# fusebox.net
KiCad netlist of a schematic drawn in EAGLE
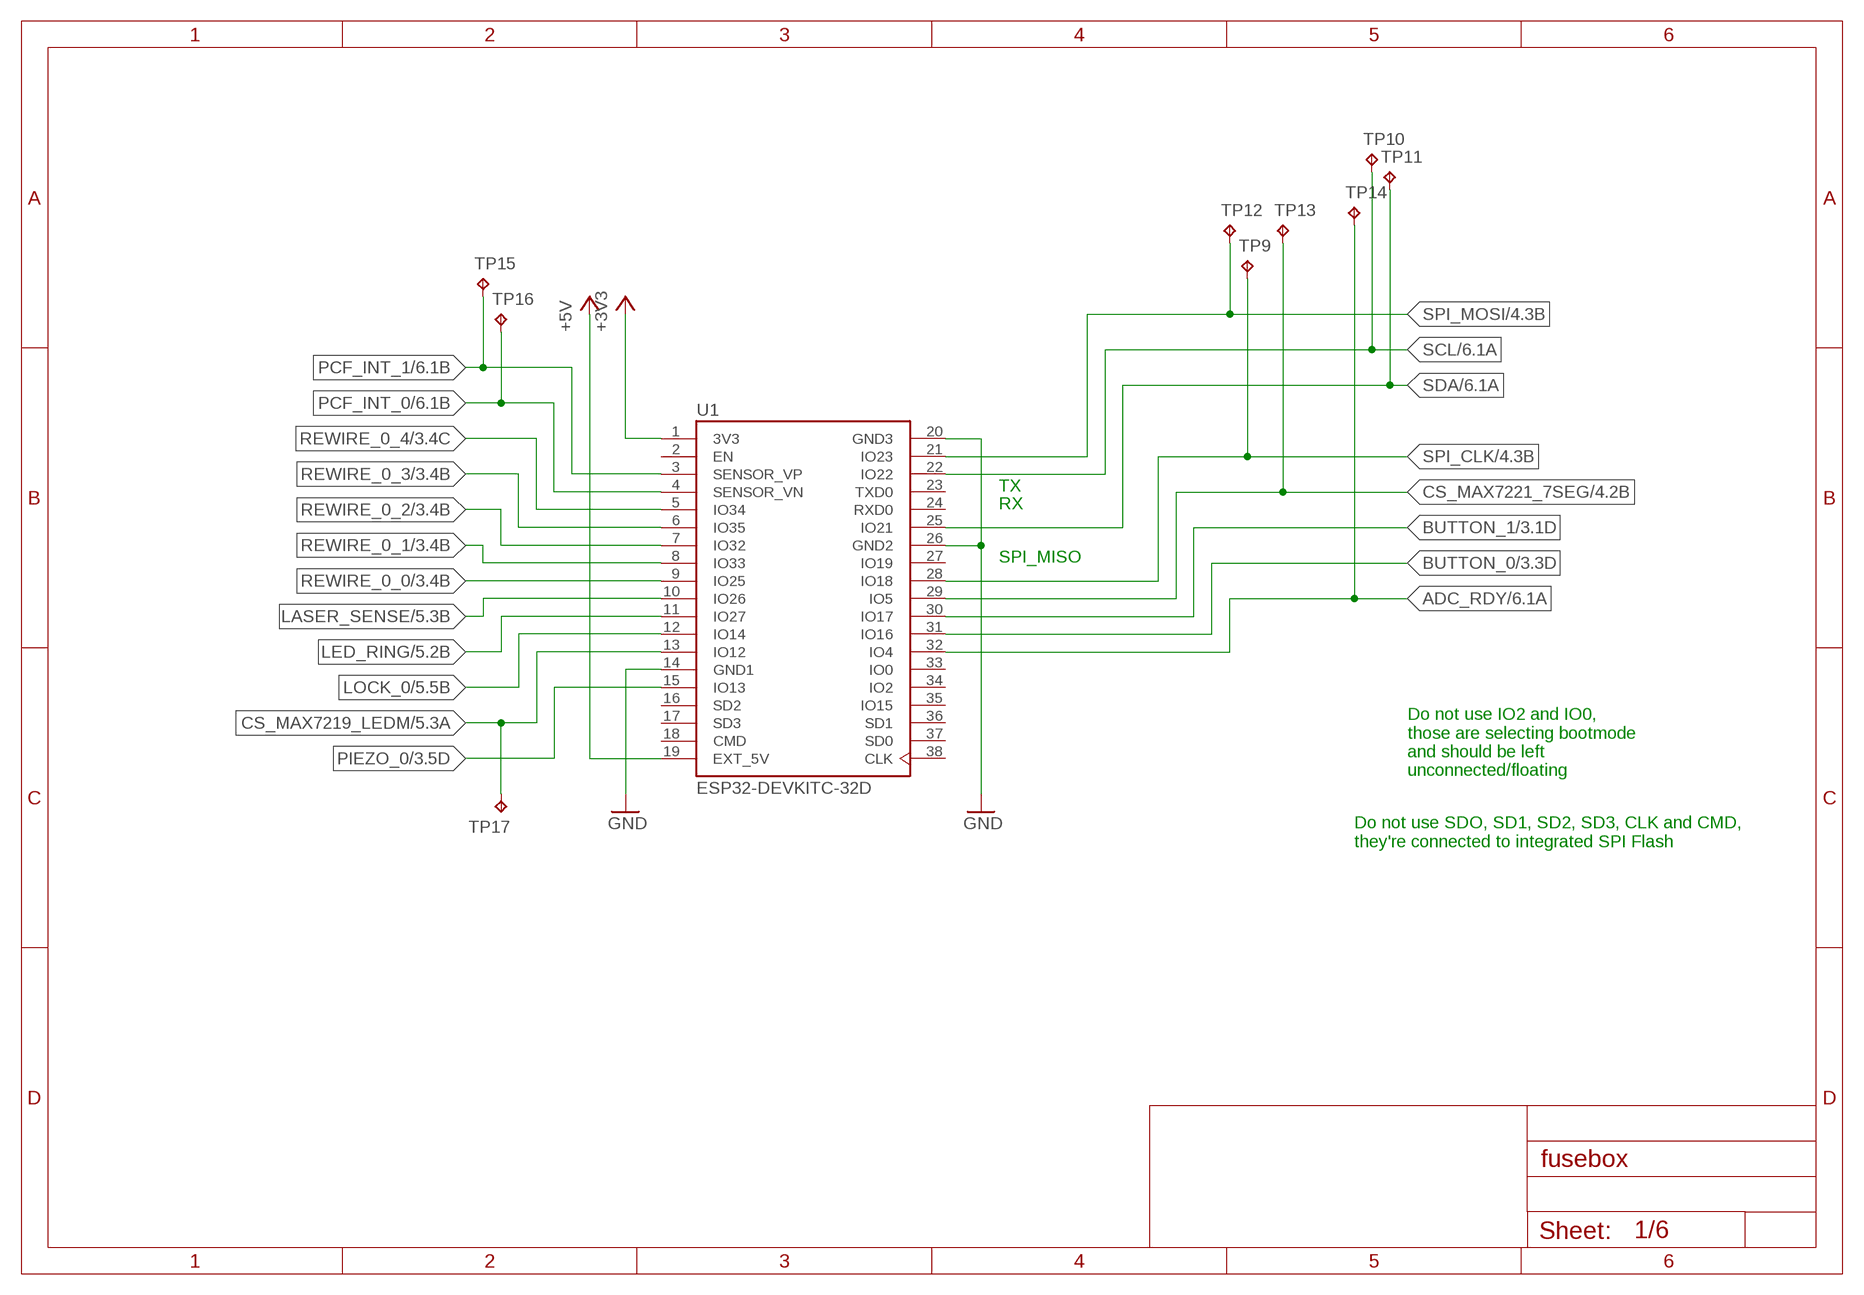
[diagram p0: schematic, sheet 1]
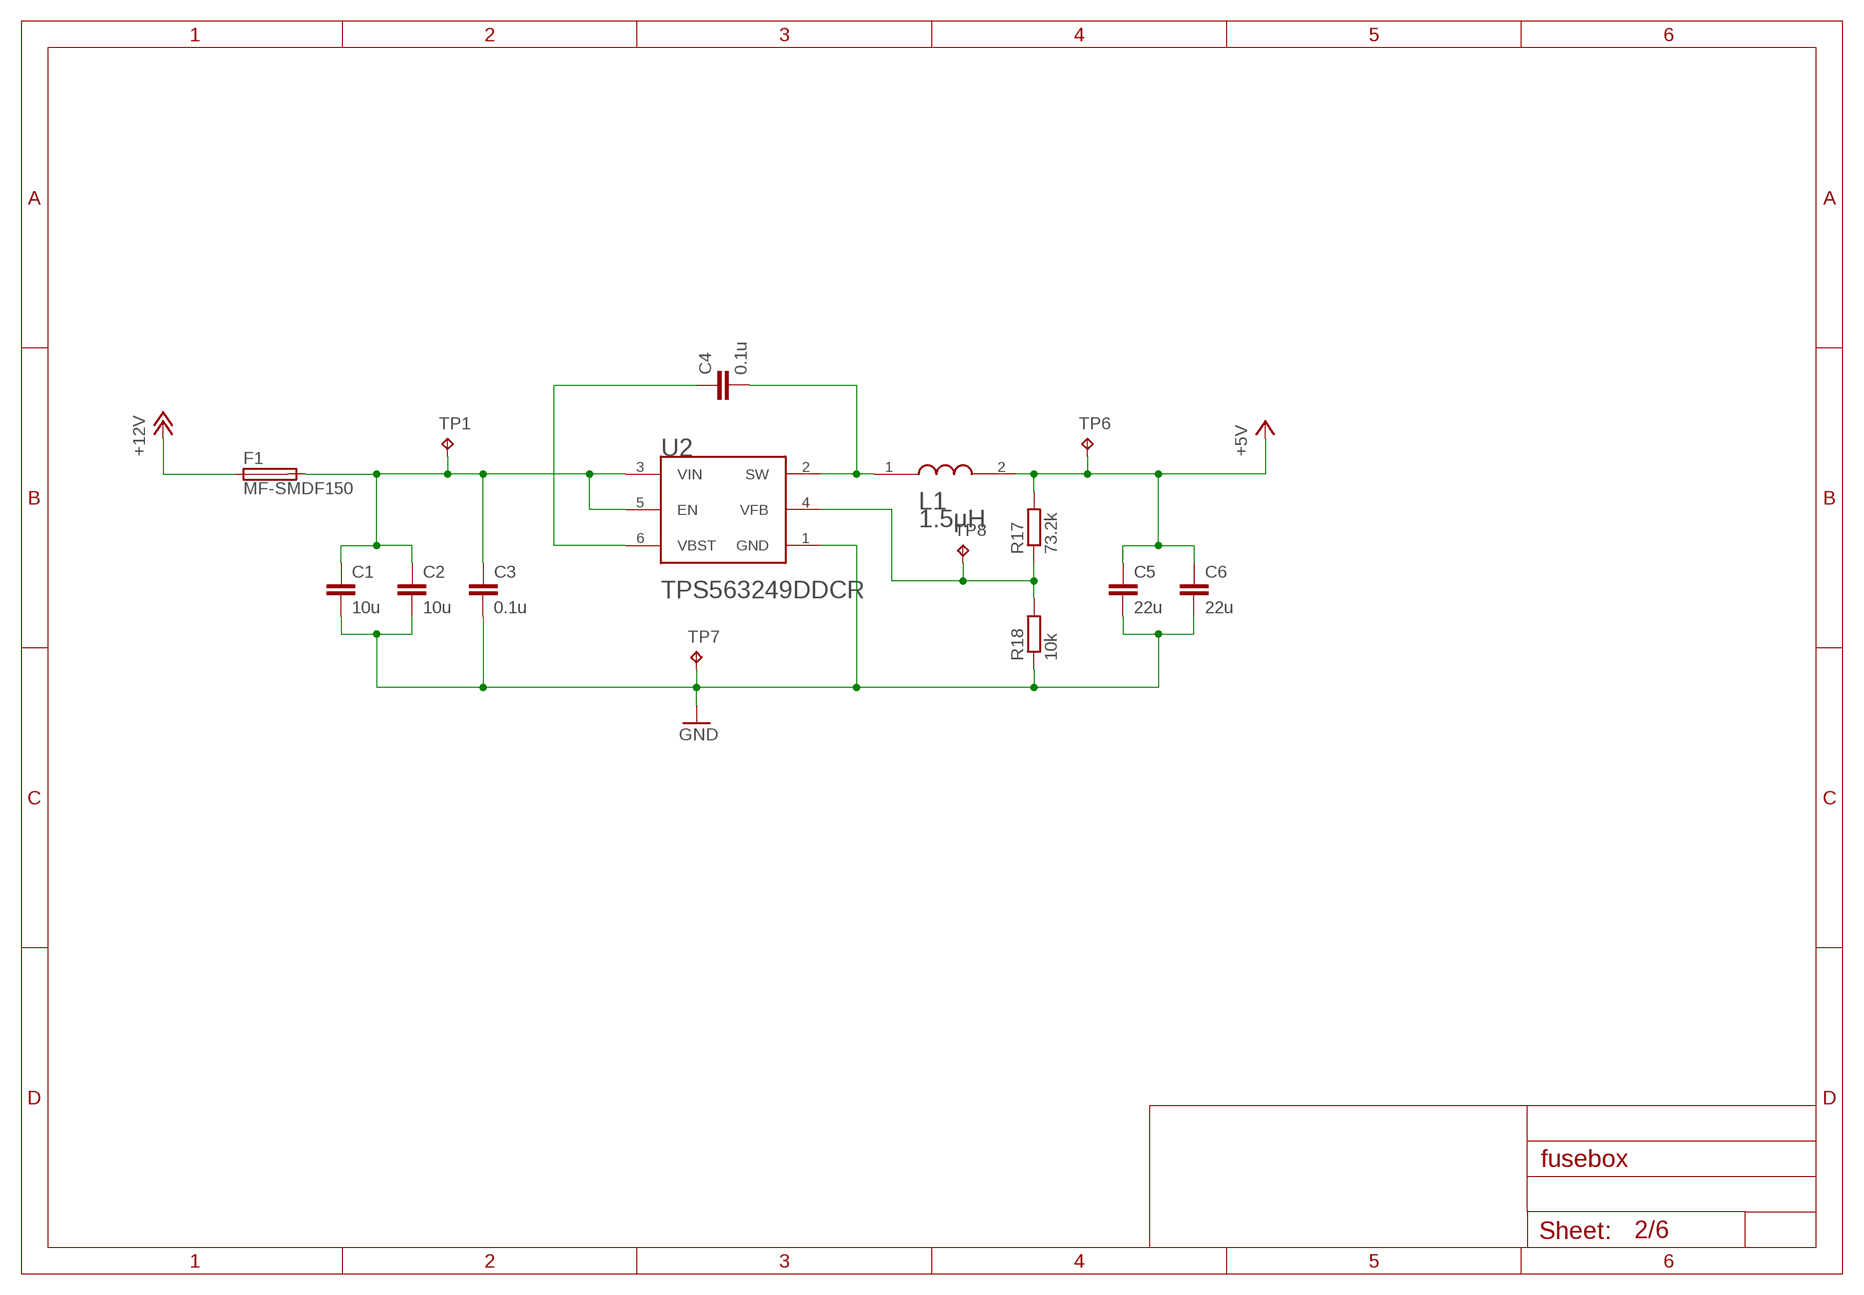
[diagram p1: schematic, sheet 2]
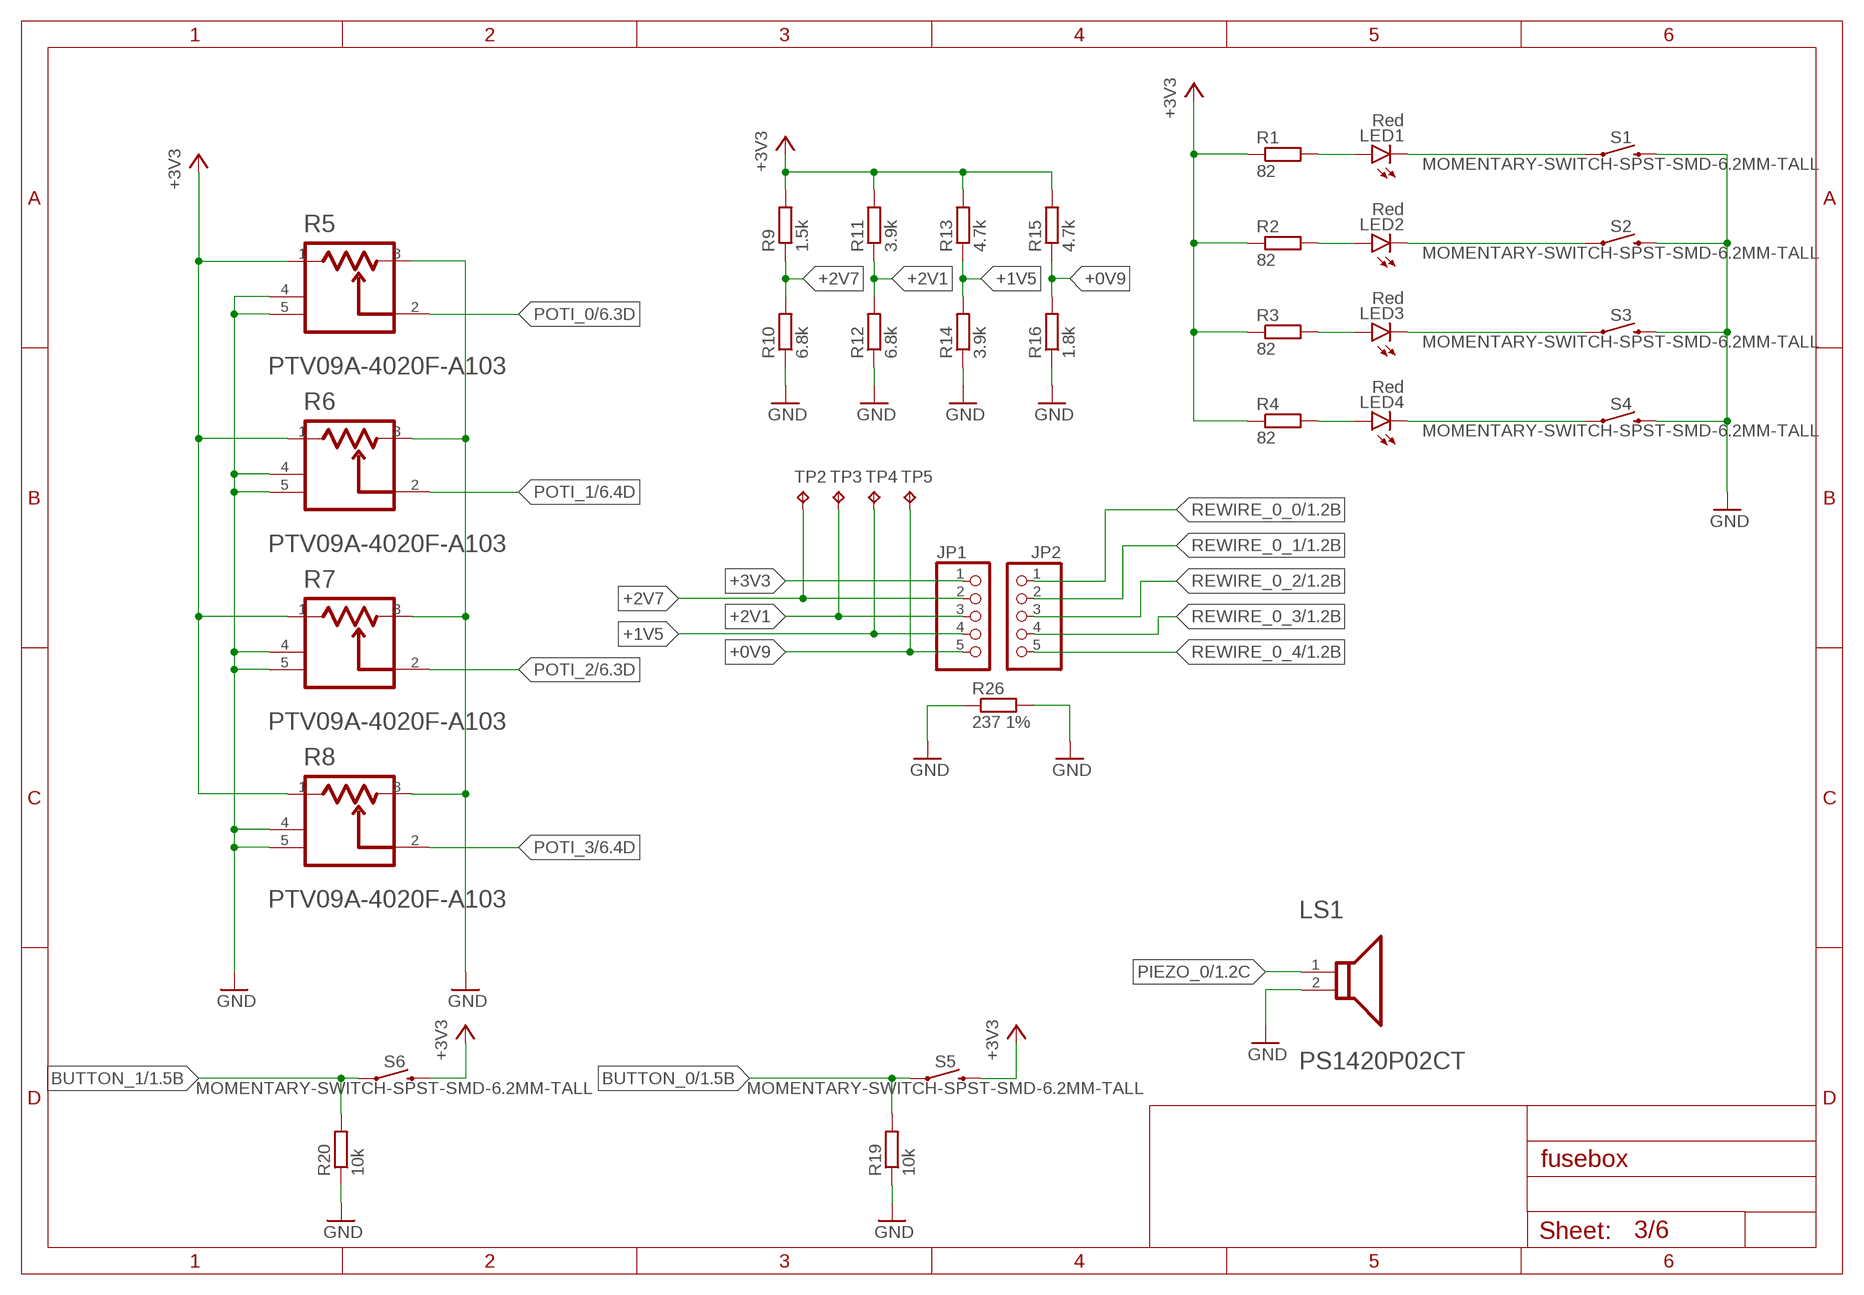
[diagram p2: schematic, sheet 3]
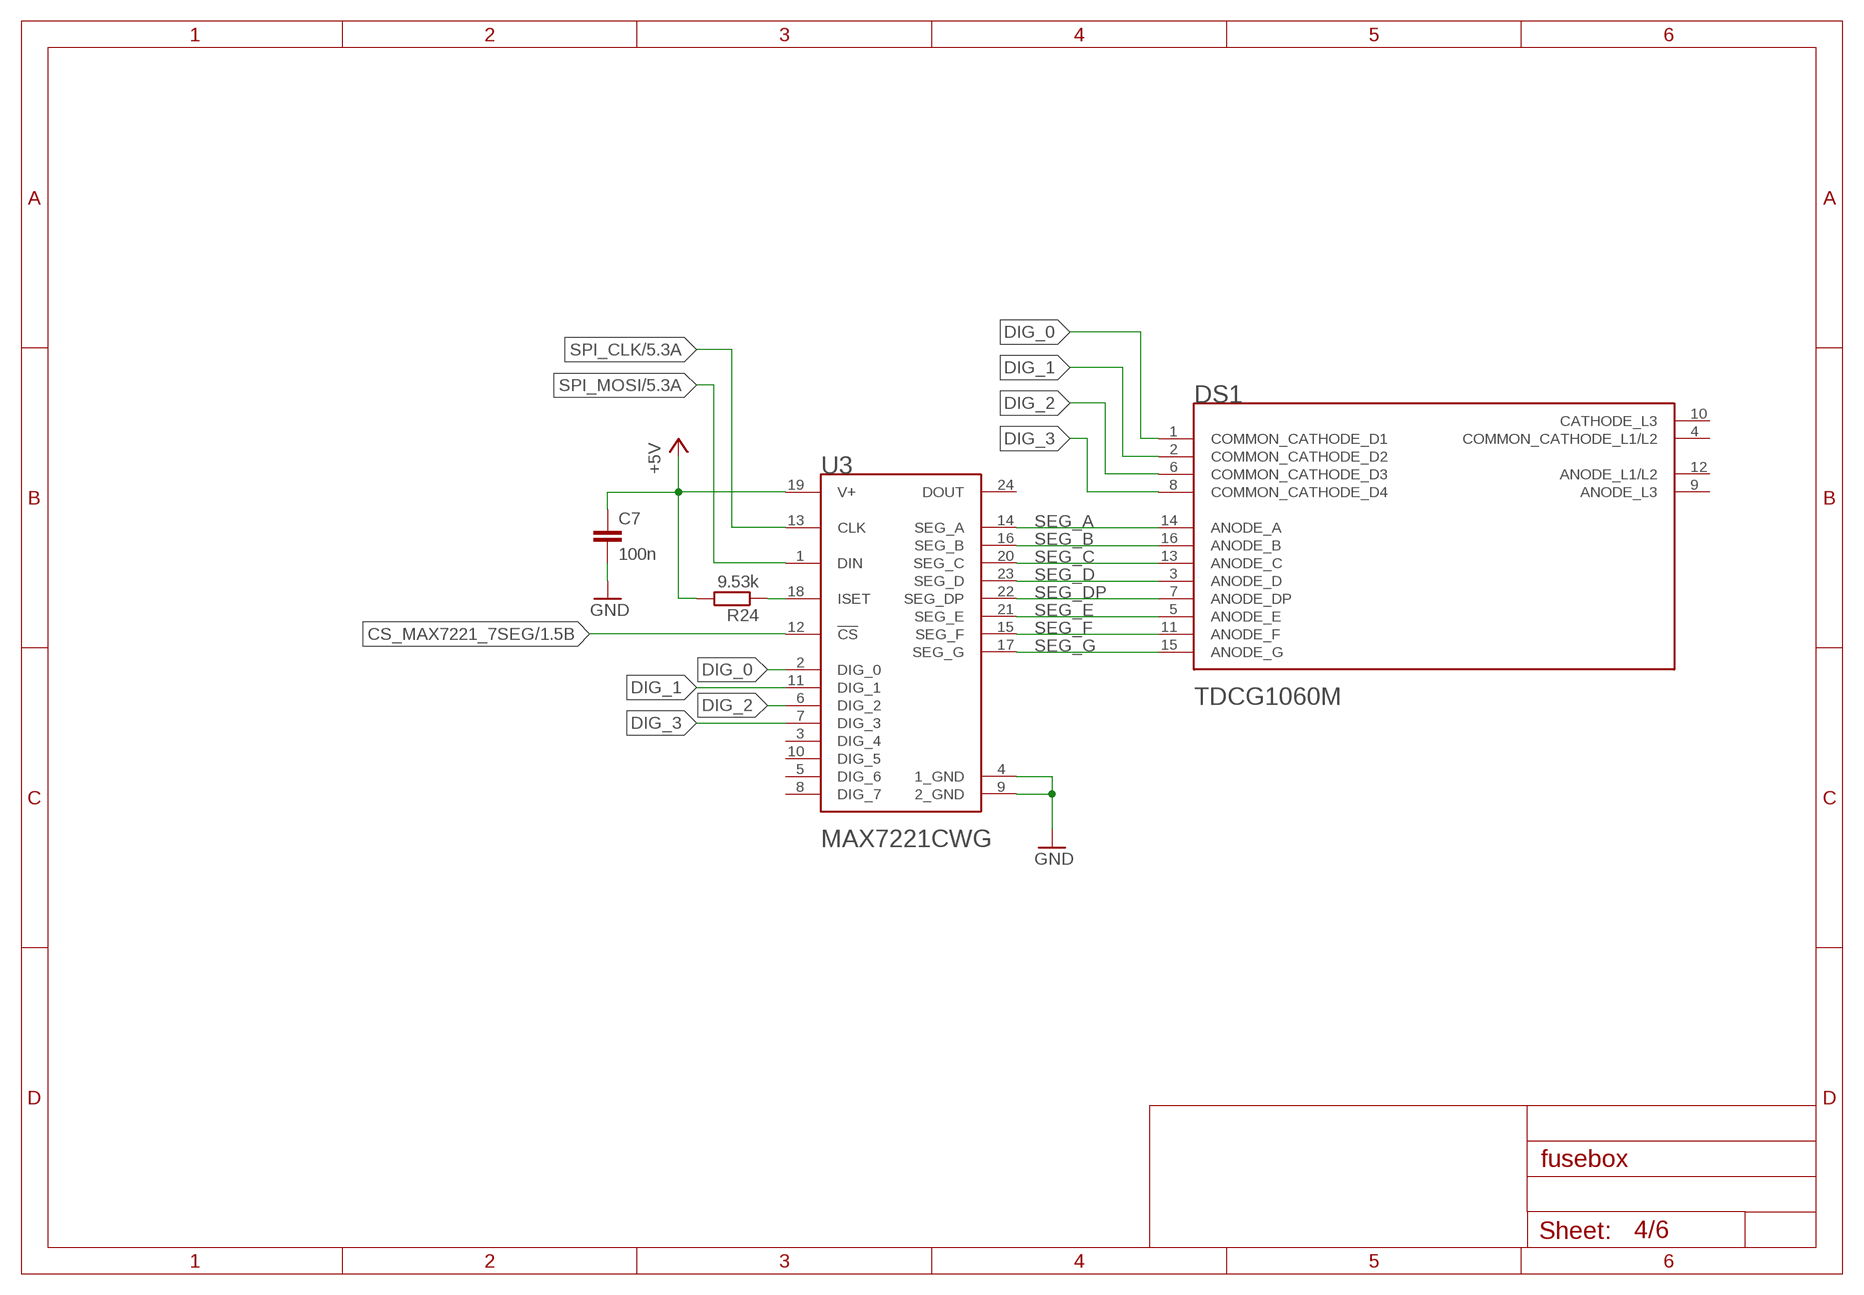
[diagram p3: schematic, sheet 4]
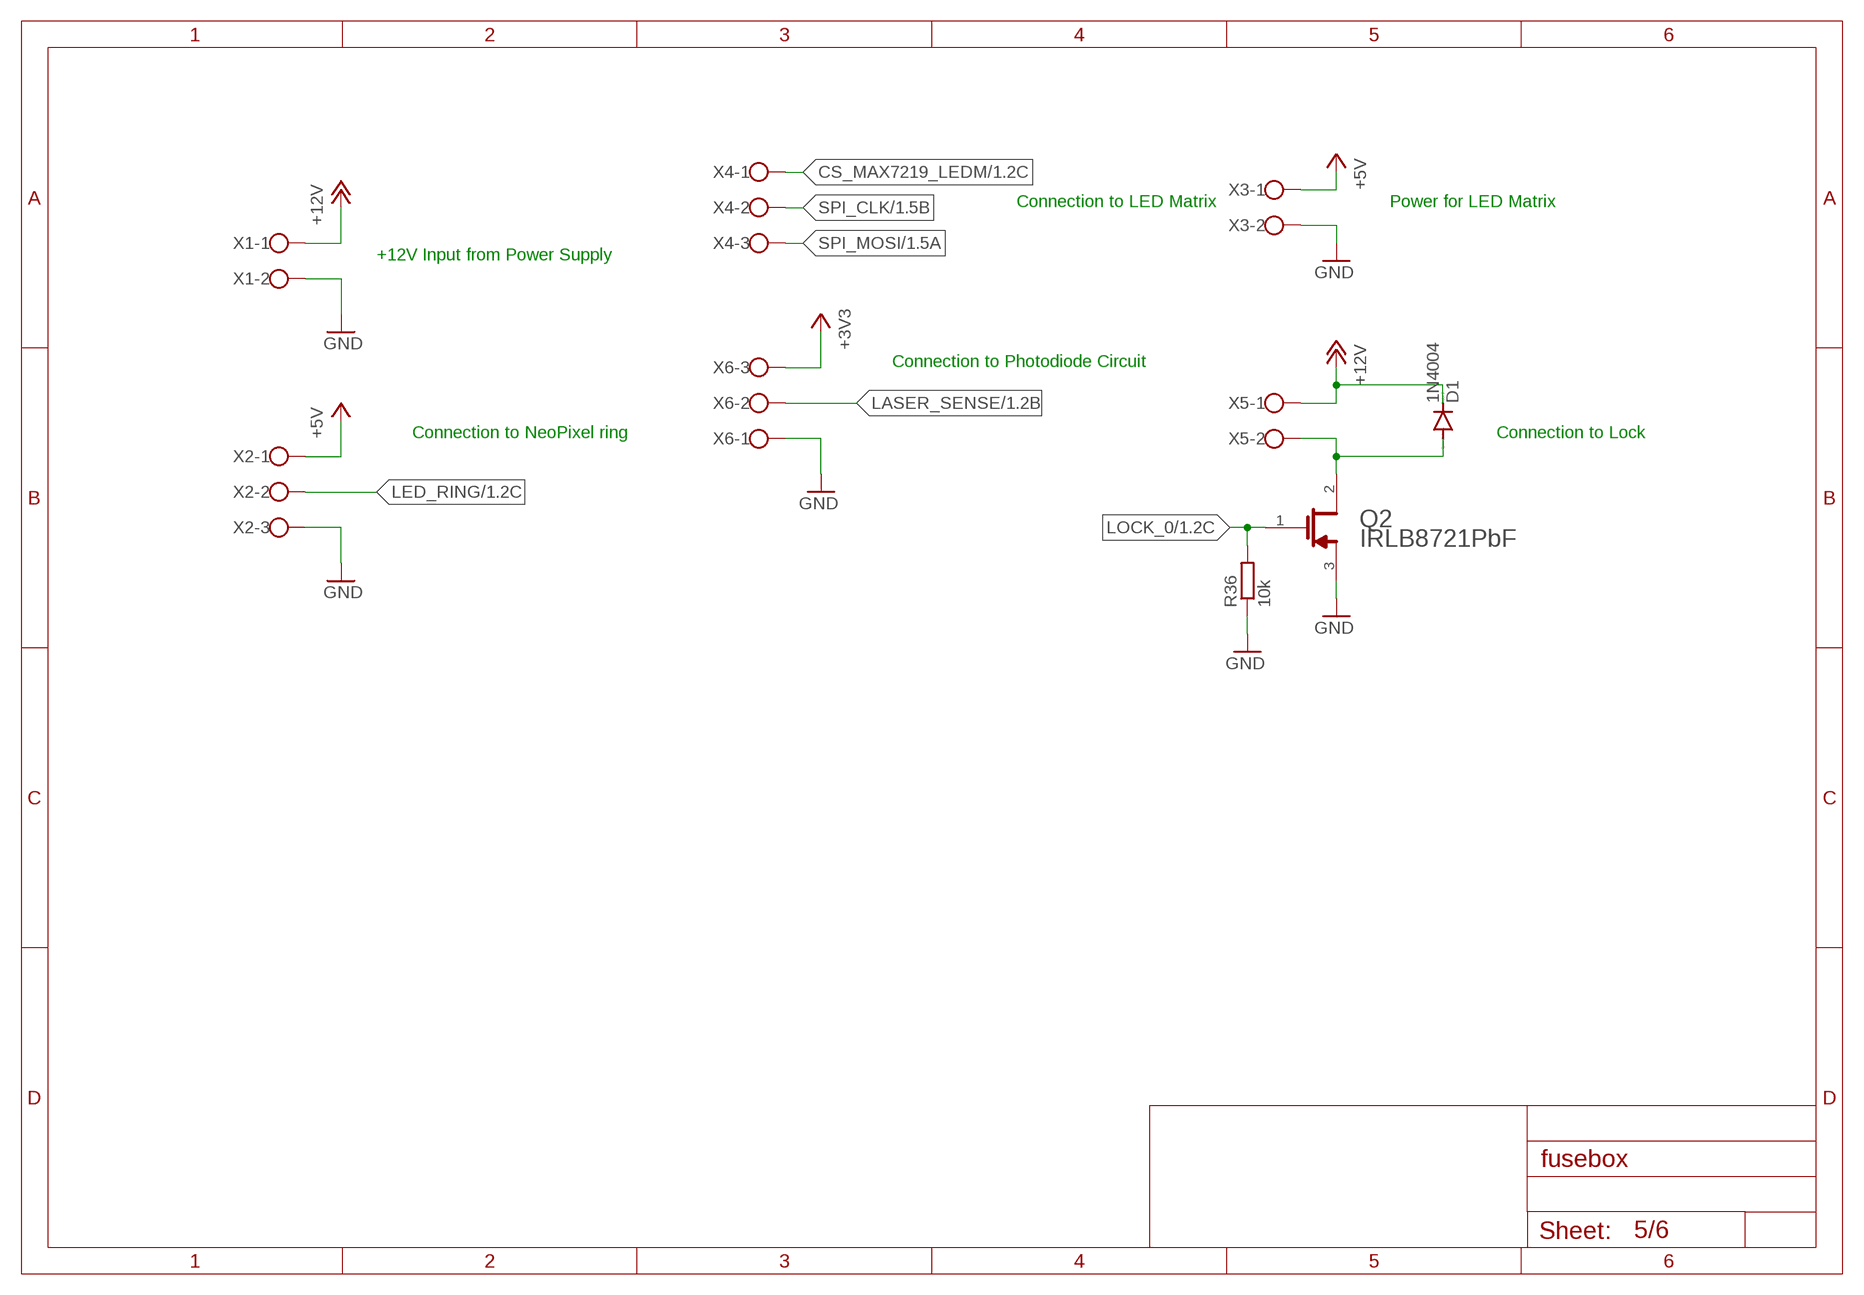
[diagram p4: schematic, sheet 5]
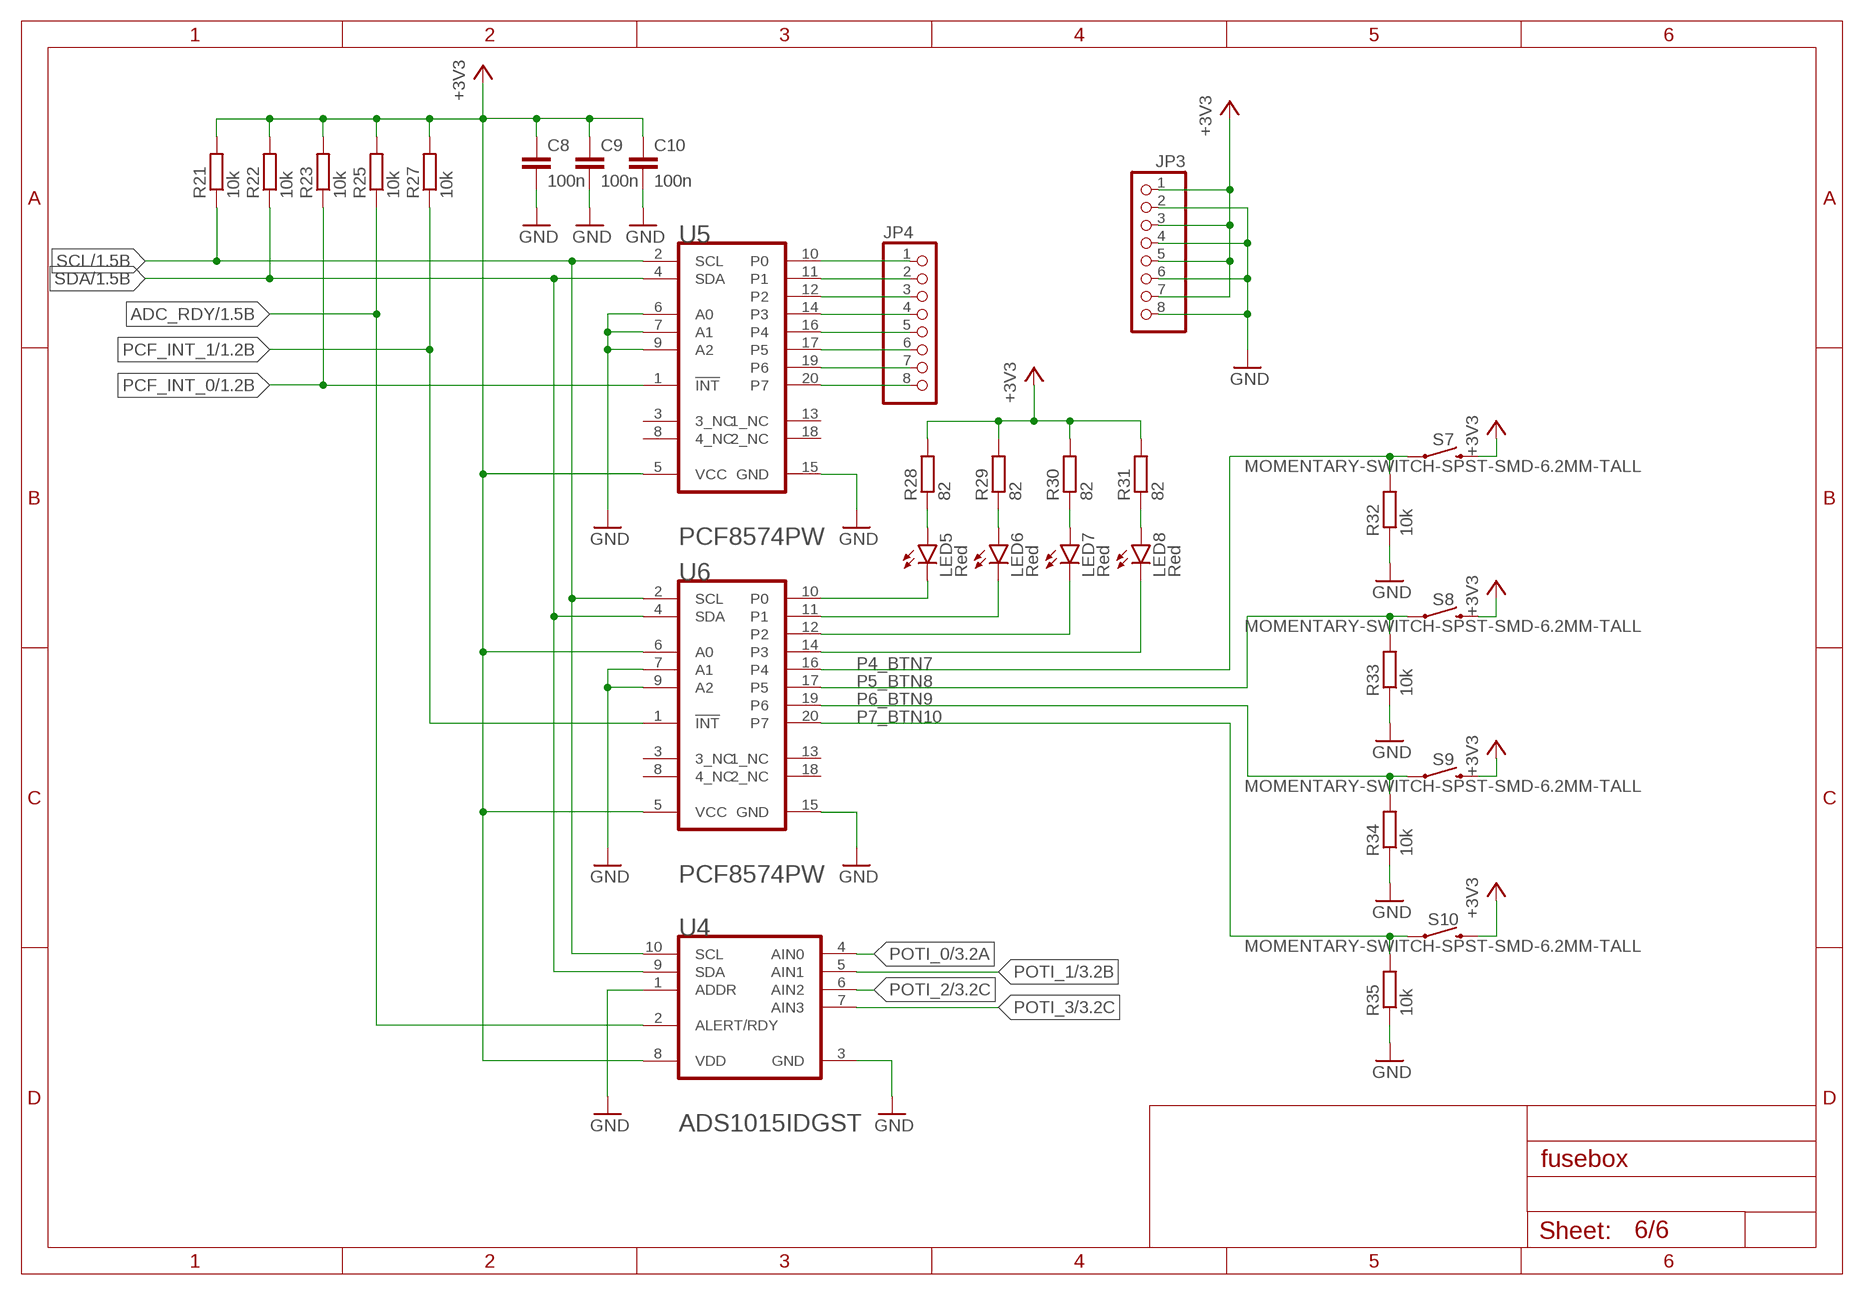
[diagram p5: schematic, sheet 6]

(export (version "E")
  (design (tool "Eeschema 10.0.6"))
  (components
    (comp (ref "D1")
      (value "1N4004")
      (footprint "eagle-import:DO41-10")
      (libsource (lib "eagle-import") (part "1N4004"))
    )
    (comp (ref "Q2")
      (value "INFINEON_IRLB8721PBFINFINEON_IRLB8721PBF_0_0")
      (footprint "eagle-import:INFINEON_IRLB8721PBF_0")
      (fields
        (field (name "DIGIKEY_PART_NUMBER") "IRLB8721PBF-ND")
        (field (name "MF") "Infineon")
        (field (name "MOUSER_PART_NUMBER") "942-IRLB8721PBF")
      )
      (libsource (lib "eagle-import") (part "INFINEON_IRLB8721PBFINFINEON_IRLB8721PBF_0_0"))
    )
    (comp (ref "R36")
      (value "10k")
      (footprint "eagle-import:R0805")
      (libsource (lib "eagle-import") (part "R-EU_R0805"))
    )
    (comp (ref "X1")
      (value "W237-102")
      (footprint "eagle-import:W237-102")
      (fields (field (name "MPN") "237-102"))
      (libsource (lib "eagle-import") (part "W237-102"))
    )
    (comp (ref "X2")
      (value "W237-103")
      (footprint "eagle-import:W237-103")
      (fields (field (name "MPN") "237-103"))
      (libsource (lib "eagle-import") (part "W237-103"))
    )
    (comp (ref "X3")
      (value "W237-102")
      (footprint "eagle-import:W237-102")
      (fields (field (name "MPN") "237-102"))
      (libsource (lib "eagle-import") (part "W237-102"))
    )
    (comp (ref "X4")
      (value "W237-103")
      (footprint "eagle-import:W237-103")
      (fields (field (name "MPN") "237-103"))
      (libsource (lib "eagle-import") (part "W237-103"))
    )
    (comp (ref "X5")
      (value "W237-102")
      (footprint "eagle-import:W237-102")
      (fields (field (name "MPN") "237-102"))
      (libsource (lib "eagle-import") (part "W237-102"))
    )
    (comp (ref "X6")
      (value "W237-103")
      (footprint "eagle-import:W237-103")
      (fields (field (name "MPN") "237-103"))
      (libsource (lib "eagle-import") (part "W237-103"))
    )
    (comp (ref "TP9")
      (value "TPB1,27")
      (footprint "eagle-import:B1,27")
      (libsource (lib "eagle-import") (part "TPB1,27"))
    )
    (comp (ref "TP10")
      (value "TPB1,27")
      (footprint "eagle-import:B1,27")
      (libsource (lib "eagle-import") (part "TPB1,27"))
    )
    (comp (ref "TP11")
      (value "TPB1,27")
      (footprint "eagle-import:B1,27")
      (libsource (lib "eagle-import") (part "TPB1,27"))
    )
    (comp (ref "TP12")
      (value "TPB1,27")
      (footprint "eagle-import:B1,27")
      (libsource (lib "eagle-import") (part "TPB1,27"))
    )
    (comp (ref "TP13")
      (value "TPB1,27")
      (footprint "eagle-import:B1,27")
      (libsource (lib "eagle-import") (part "TPB1,27"))
    )
    (comp (ref "TP14")
      (value "TPB1,27")
      (footprint "eagle-import:B1,27")
      (libsource (lib "eagle-import") (part "TPB1,27"))
    )
    (comp (ref "TP15")
      (value "TPB1,27")
      (footprint "eagle-import:B1,27")
      (libsource (lib "eagle-import") (part "TPB1,27"))
    )
    (comp (ref "TP16")
      (value "TPB1,27")
      (footprint "eagle-import:B1,27")
      (libsource (lib "eagle-import") (part "TPB1,27"))
    )
    (comp (ref "TP17")
      (value "TPB1,27")
      (footprint "eagle-import:B1,27")
      (libsource (lib "eagle-import") (part "TPB1,27"))
    )
    (comp (ref "U1")
      (value "ESP32-DEVKITC-32D")
      (footprint "eagle-import:MODULE_ESP32-DEVKITC-32D")
      (fields (field (name "MF") "Espressif Systems"))
      (libsource (lib "eagle-import") (part "ESP32-DEVKITC-32D"))
    )
    (comp (ref "C1")
      (value "10u")
      (footprint "eagle-import:C1206")
      (libsource (lib "eagle-import") (part "C-EUC1206"))
    )
    (comp (ref "C2")
      (value "10u")
      (footprint "eagle-import:C1206")
      (libsource (lib "eagle-import") (part "C-EUC1206"))
    )
    (comp (ref "C3")
      (value "0.1u")
      (footprint "eagle-import:C0603K")
      (libsource (lib "eagle-import") (part "C-EUC0603K"))
    )
    (comp (ref "C4")
      (value "0.1u")
      (footprint "eagle-import:C0603")
      (libsource (lib "eagle-import") (part "C-EUC0603"))
    )
    (comp (ref "C5")
      (value "22u")
      (footprint "eagle-import:C0603")
      (libsource (lib "eagle-import") (part "C-EUC0603"))
    )
    (comp (ref "C6")
      (value "22u")
      (footprint "eagle-import:C0603")
      (libsource (lib "eagle-import") (part "C-EUC0603"))
    )
    (comp (ref "F1")
      (value "MF-SMDF150")
      (footprint "eagle-import:MF-SMDF050")
      (libsource (lib "eagle-import") (part "MF-SMDF150"))
    )
    (comp (ref "L1")
      (value "BOURNS_SRN8040-1R5YBOURNS_SRN8040-1R5Y_0_0")
      (footprint "eagle-import:BOURNS_SRN8040-1R5Y_0")
      (fields
        (field (name "DIGIKEY_PART_NUMBER") "SRN8040-1R5YCT-ND")
        (field (name "MF") "Bourns")
        (field (name "MOUSER_PART_NUMBER") "652-SRN8040-1R5Y")
      )
      (libsource (lib "eagle-import") (part "BOURNS_SRN8040-1R5YBOURNS_SRN8040-1R5Y_0_0"))
    )
    (comp (ref "R17")
      (value "73.2k")
      (footprint "eagle-import:R0402")
      (libsource (lib "eagle-import") (part "R-EU_R0402"))
    )
    (comp (ref "R18")
      (value "10k")
      (footprint "eagle-import:R0201")
      (libsource (lib "eagle-import") (part "R-EU_R0201"))
    )
    (comp (ref "TP1")
      (value "TPB1,27")
      (footprint "eagle-import:B1,27")
      (libsource (lib "eagle-import") (part "TPB1,27"))
    )
    (comp (ref "TP6")
      (value "TPB1,27")
      (footprint "eagle-import:B1,27")
      (libsource (lib "eagle-import") (part "TPB1,27"))
    )
    (comp (ref "TP7")
      (value "TPB1,27")
      (footprint "eagle-import:B1,27")
      (libsource (lib "eagle-import") (part "TPB1,27"))
    )
    (comp (ref "TP8")
      (value "TPB1,27")
      (footprint "eagle-import:B1,27")
      (libsource (lib "eagle-import") (part "TPB1,27"))
    )
    (comp (ref "U2")
      (value "TEXAS_INSTRUMENTS_TPS563249DDCRTEXAS_INSTRUMENTS_TPS563249DDCR_0_0")
      (footprint "eagle-import:TEXAS_INSTRUMENTS_TPS563249DDCR_0")
      (fields
        (field (name "DIGIKEY_PART_NUMBER") "296-53452-1-ND")
        (field (name "MF") "Texas Instruments")
        (field (name "MOUSER_PART_NUMBER") "595-TPS563249DDCR")
      )
      (libsource (lib "eagle-import") (part "TEXAS_INSTRUMENTS_TPS563249DDCRTEXAS_INSTRUMENTS_TPS563249DDCR_0_0"))
    )
    (comp (ref "C8")
      (value "100n")
      (footprint "eagle-import:C0805K")
      (libsource (lib "eagle-import") (part "C-EUC0805K"))
    )
    (comp (ref "C9")
      (value "100n")
      (footprint "eagle-import:C0805K")
      (libsource (lib "eagle-import") (part "C-EUC0805K"))
    )
    (comp (ref "C10")
      (value "100n")
      (footprint "eagle-import:C0805K")
      (libsource (lib "eagle-import") (part "C-EUC0805K"))
    )
    (comp (ref "JP3")
      (value "PINHD-1X8")
      (footprint "eagle-import:1X08")
      (libsource (lib "eagle-import") (part "PINHD-1X8"))
    )
    (comp (ref "JP4")
      (value "PINHD-1X8")
      (footprint "eagle-import:1X08")
      (libsource (lib "eagle-import") (part "PINHD-1X8"))
    )
    (comp (ref "LED5")
      (value "Red")
      (footprint "eagle-import:CHIP-LED0805")
      (libsource (lib "eagle-import") (part "LEDCHIP-LED0805"))
    )
    (comp (ref "LED6")
      (value "Red")
      (footprint "eagle-import:CHIP-LED0805")
      (libsource (lib "eagle-import") (part "LEDCHIP-LED0805"))
    )
    (comp (ref "LED7")
      (value "Red")
      (footprint "eagle-import:CHIP-LED0805")
      (libsource (lib "eagle-import") (part "LEDCHIP-LED0805"))
    )
    (comp (ref "LED8")
      (value "Red")
      (footprint "eagle-import:CHIP-LED0805")
      (libsource (lib "eagle-import") (part "LEDCHIP-LED0805"))
    )
    (comp (ref "R21")
      (value "10k")
      (footprint "eagle-import:R0805")
      (libsource (lib "eagle-import") (part "R-EU_R0805"))
    )
    (comp (ref "R22")
      (value "10k")
      (footprint "eagle-import:R0805")
      (libsource (lib "eagle-import") (part "R-EU_R0805"))
    )
    (comp (ref "R23")
      (value "10k")
      (footprint "eagle-import:R0805")
      (libsource (lib "eagle-import") (part "R-EU_R0805"))
    )
    (comp (ref "R25")
      (value "10k")
      (footprint "eagle-import:R0805")
      (libsource (lib "eagle-import") (part "R-EU_R0805"))
    )
    (comp (ref "R27")
      (value "10k")
      (footprint "eagle-import:R0805")
      (libsource (lib "eagle-import") (part "R-EU_R0805"))
    )
    (comp (ref "R28")
      (value "82")
      (footprint "eagle-import:R0805")
      (libsource (lib "eagle-import") (part "R-EU_R0805"))
    )
    (comp (ref "R29")
      (value "82")
      (footprint "eagle-import:R0805")
      (libsource (lib "eagle-import") (part "R-EU_R0805"))
    )
    (comp (ref "R30")
      (value "82")
      (footprint "eagle-import:R0805")
      (libsource (lib "eagle-import") (part "R-EU_R0805"))
    )
    (comp (ref "R31")
      (value "82")
      (footprint "eagle-import:R0805")
      (libsource (lib "eagle-import") (part "R-EU_R0805"))
    )
    (comp (ref "R32")
      (value "10k")
      (footprint "eagle-import:R0805")
      (libsource (lib "eagle-import") (part "R-EU_R0805"))
    )
    (comp (ref "R33")
      (value "10k")
      (footprint "eagle-import:R0805")
      (libsource (lib "eagle-import") (part "R-EU_R0805"))
    )
    (comp (ref "R34")
      (value "10k")
      (footprint "eagle-import:R0805")
      (libsource (lib "eagle-import") (part "R-EU_R0805"))
    )
    (comp (ref "R35")
      (value "10k")
      (footprint "eagle-import:R0805")
      (libsource (lib "eagle-import") (part "R-EU_R0805"))
    )
    (comp (ref "S7")
      (value "MOMENTARY-SWITCH-SPST-SMD-6.2MM-TALL")
      (footprint "eagle-import:TACTILE_SWITCH_SMD_6.2MM_TALL")
      (libsource (lib "eagle-import") (part "MOMENTARY-SWITCH-SPST-SMD-6.2MM-TALL"))
    )
    (comp (ref "S8")
      (value "MOMENTARY-SWITCH-SPST-SMD-6.2MM-TALL")
      (footprint "eagle-import:TACTILE_SWITCH_SMD_6.2MM_TALL")
      (libsource (lib "eagle-import") (part "MOMENTARY-SWITCH-SPST-SMD-6.2MM-TALL"))
    )
    (comp (ref "S9")
      (value "MOMENTARY-SWITCH-SPST-SMD-6.2MM-TALL")
      (footprint "eagle-import:TACTILE_SWITCH_SMD_6.2MM_TALL")
      (libsource (lib "eagle-import") (part "MOMENTARY-SWITCH-SPST-SMD-6.2MM-TALL"))
    )
    (comp (ref "S10")
      (value "MOMENTARY-SWITCH-SPST-SMD-6.2MM-TALL")
      (footprint "eagle-import:TACTILE_SWITCH_SMD_6.2MM_TALL")
      (libsource (lib "eagle-import") (part "MOMENTARY-SWITCH-SPST-SMD-6.2MM-TALL"))
    )
    (comp (ref "U4")
      (value "TEXAS_INSTRUMENTS_ADS1015IDGSTTEXAS_INSTRUMENTS_ADS1015IDGST_0_0")
      (footprint "eagle-import:TEXAS_INSTRUMENTS_ADS1015IDGST_0")
      (fields (field (name "MF") "Texas Instruments") (field (name "MPN") "ADS1015IDGST"))
      (libsource (lib "eagle-import") (part "TEXAS_INSTRUMENTS_ADS1015IDGSTTEXAS_INSTRUMENTS_ADS1015IDGST_0_0"))
    )
    (comp (ref "U5")
      (value "TEXAS_INSTRUMENTS_PCF8574PWTEXAS_INSTRUMENTS_PCF8574PW_0_0")
      (footprint "eagle-import:TEXAS_INSTRUMENTS_PCF8574PW_0")
      (fields (field (name "MF") "Texas Instruments") (field (name "MPN") "PCF8574PW"))
      (libsource (lib "eagle-import") (part "TEXAS_INSTRUMENTS_PCF8574PWTEXAS_INSTRUMENTS_PCF8574PW_0_0"))
    )
    (comp (ref "U6")
      (value "TEXAS_INSTRUMENTS_PCF8574PWTEXAS_INSTRUMENTS_PCF8574PW_0_0")
      (footprint "eagle-import:TEXAS_INSTRUMENTS_PCF8574PW_0")
      (fields (field (name "MF") "Texas Instruments") (field (name "MPN") "PCF8574PW"))
      (libsource (lib "eagle-import") (part "TEXAS_INSTRUMENTS_PCF8574PWTEXAS_INSTRUMENTS_PCF8574PW_0_0"))
    )
    (comp (ref "C7")
      (value "100n")
      (footprint "eagle-import:C0805K")
      (libsource (lib "eagle-import") (part "C-EUC0805K"))
    )
    (comp (ref "DS1")
      (value "VISHAY_TDCG1060MVISHAY_TDCG1060M_0_0")
      (footprint "eagle-import:VISHAY_TDCG1060M_0")
      (fields
        (field (name "DIGIKEY_PART_NUMBER") "TDCG1060M-ND")
        (field (name "MF") "Vishay")
        (field (name "MOUSER_PART_NUMBER") "78-TDCG1060")
      )
      (libsource (lib "eagle-import") (part "VISHAY_TDCG1060MVISHAY_TDCG1060M_0_0"))
    )
    (comp (ref "R24")
      (value "9.53k")
      (footprint "eagle-import:R0805")
      (libsource (lib "eagle-import") (part "R-EU_R0805"))
    )
    (comp (ref "U3")
      (value "MAXIM_ELECTRONICS_MAX7221CWGMAXIM_ELECTRONICS_MAX7221CWG_0_0")
      (footprint "eagle-import:MAXIM_ELECTRONICS_MAX7221CWG_0")
      (fields
        (field (name "DIGIKEY_PART_NUMBER") "MAX7221CWG+-ND")
        (field (name "MF") "Maxim Electronics")
        (field (name "MOUSER_PART_NUMBER") "700-MAX7221CWG")
      )
      (libsource (lib "eagle-import") (part "MAXIM_ELECTRONICS_MAX7221CWGMAXIM_ELECTRONICS_MAX7221CWG_0_0"))
    )
    (comp (ref "JP1")
      (value "PINHD-1X5")
      (footprint "eagle-import:1X05")
      (libsource (lib "eagle-import") (part "PINHD-1X5"))
    )
    (comp (ref "JP2")
      (value "PINHD-1X5")
      (footprint "eagle-import:1X05")
      (libsource (lib "eagle-import") (part "PINHD-1X5"))
    )
    (comp (ref "LED1")
      (value "Red")
      (footprint "eagle-import:CHIP-LED0805")
      (libsource (lib "eagle-import") (part "LEDCHIP-LED0805"))
    )
    (comp (ref "LED2")
      (value "Red")
      (footprint "eagle-import:CHIP-LED0805")
      (libsource (lib "eagle-import") (part "LEDCHIP-LED0805"))
    )
    (comp (ref "LED3")
      (value "Red")
      (footprint "eagle-import:CHIP-LED0805")
      (libsource (lib "eagle-import") (part "LEDCHIP-LED0805"))
    )
    (comp (ref "LED4")
      (value "Red")
      (footprint "eagle-import:CHIP-LED0805")
      (libsource (lib "eagle-import") (part "LEDCHIP-LED0805"))
    )
    (comp (ref "LS1")
      (value "TDK_PS1420P02CTTDK_PS1420P02CT_0_0")
      (footprint "eagle-import:TDK_PS1420P02CT_0")
      (fields
        (field (name "DIGIKEY_PART_NUMBER") "445-2526-1-ND")
        (field (name "MF") "TDK")
        (field (name "MOUSER_PART_NUMBER") "810-PS1420P02CT")
      )
      (libsource (lib "eagle-import") (part "TDK_PS1420P02CTTDK_PS1420P02CT_0_0"))
    )
    (comp (ref "R1")
      (value "82")
      (footprint "eagle-import:R0805")
      (libsource (lib "eagle-import") (part "R-EU_R0805"))
    )
    (comp (ref "R2")
      (value "82")
      (footprint "eagle-import:R0805")
      (libsource (lib "eagle-import") (part "R-EU_R0805"))
    )
    (comp (ref "R3")
      (value "82")
      (footprint "eagle-import:R0805")
      (libsource (lib "eagle-import") (part "R-EU_R0805"))
    )
    (comp (ref "R4")
      (value "82")
      (footprint "eagle-import:R0805")
      (libsource (lib "eagle-import") (part "R-EU_R0805"))
    )
    (comp (ref "R5")
      (value "BOURNS_PTV09A-4020F-A103BOURNS_PTV09A-4020F-A103_0_0")
      (footprint "eagle-import:BOURNS_PTV09A-4020F-A103_0")
      (fields
        (field (name "DIGIKEY_PART_NUMBER") "PTV09A-4020F-A103-ND")
        (field (name "MF") "Bourns")
        (field (name "MOUSER_PART_NUMBER") "652-PTV09A-4020FA103")
      )
      (libsource (lib "eagle-import") (part "BOURNS_PTV09A-4020F-A103BOURNS_PTV09A-4020F-A103_0_0"))
    )
    (comp (ref "R6")
      (value "BOURNS_PTV09A-4020F-A103BOURNS_PTV09A-4020F-A103_0_0")
      (footprint "eagle-import:BOURNS_PTV09A-4020F-A103_0")
      (fields
        (field (name "DIGIKEY_PART_NUMBER") "PTV09A-4020F-A103-ND")
        (field (name "MF") "Bourns")
        (field (name "MOUSER_PART_NUMBER") "652-PTV09A-4020FA103")
      )
      (libsource (lib "eagle-import") (part "BOURNS_PTV09A-4020F-A103BOURNS_PTV09A-4020F-A103_0_0"))
    )
    (comp (ref "R7")
      (value "BOURNS_PTV09A-4020F-A103BOURNS_PTV09A-4020F-A103_0_0")
      (footprint "eagle-import:BOURNS_PTV09A-4020F-A103_0")
      (fields
        (field (name "DIGIKEY_PART_NUMBER") "PTV09A-4020F-A103-ND")
        (field (name "MF") "Bourns")
        (field (name "MOUSER_PART_NUMBER") "652-PTV09A-4020FA103")
      )
      (libsource (lib "eagle-import") (part "BOURNS_PTV09A-4020F-A103BOURNS_PTV09A-4020F-A103_0_0"))
    )
    (comp (ref "R8")
      (value "BOURNS_PTV09A-4020F-A103BOURNS_PTV09A-4020F-A103_0_0")
      (footprint "eagle-import:BOURNS_PTV09A-4020F-A103_0")
      (fields
        (field (name "DIGIKEY_PART_NUMBER") "PTV09A-4020F-A103-ND")
        (field (name "MF") "Bourns")
        (field (name "MOUSER_PART_NUMBER") "652-PTV09A-4020FA103")
      )
      (libsource (lib "eagle-import") (part "BOURNS_PTV09A-4020F-A103BOURNS_PTV09A-4020F-A103_0_0"))
    )
    (comp (ref "R9")
      (value "1.5k")
      (footprint "eagle-import:R0805")
      (libsource (lib "eagle-import") (part "R-EU_R0805"))
    )
    (comp (ref "R10")
      (value "6.8k")
      (footprint "eagle-import:R0805")
      (libsource (lib "eagle-import") (part "R-EU_R0805"))
    )
    (comp (ref "R11")
      (value "3.9k")
      (footprint "eagle-import:R0805")
      (libsource (lib "eagle-import") (part "R-EU_R0805"))
    )
    (comp (ref "R12")
      (value "6.8k")
      (footprint "eagle-import:R0805")
      (libsource (lib "eagle-import") (part "R-EU_R0805"))
    )
    (comp (ref "R13")
      (value "4.7k")
      (footprint "eagle-import:R0805")
      (libsource (lib "eagle-import") (part "R-EU_R0805"))
    )
    (comp (ref "R14")
      (value "3.9k")
      (footprint "eagle-import:R0805")
      (libsource (lib "eagle-import") (part "R-EU_R0805"))
    )
    (comp (ref "R15")
      (value "4.7k")
      (footprint "eagle-import:R0805")
      (libsource (lib "eagle-import") (part "R-EU_R0805"))
    )
    (comp (ref "R16")
      (value "1.8k")
      (footprint "eagle-import:R0805")
      (libsource (lib "eagle-import") (part "R-EU_R0805"))
    )
    (comp (ref "R19")
      (value "10k")
      (footprint "eagle-import:R0805")
      (libsource (lib "eagle-import") (part "R-EU_R0805"))
    )
    (comp (ref "R20")
      (value "10k")
      (footprint "eagle-import:R0805")
      (libsource (lib "eagle-import") (part "R-EU_R0805"))
    )
    (comp (ref "R26")
      (value "237 1%")
      (footprint "eagle-import:0411_15")
      (libsource (lib "eagle-import") (part "R-EU_0411/15"))
    )
    (comp (ref "S1")
      (value "MOMENTARY-SWITCH-SPST-SMD-6.2MM-TALL")
      (footprint "eagle-import:TACTILE_SWITCH_SMD_6.2MM_TALL")
      (libsource (lib "eagle-import") (part "MOMENTARY-SWITCH-SPST-SMD-6.2MM-TALL"))
    )
    (comp (ref "S2")
      (value "MOMENTARY-SWITCH-SPST-SMD-6.2MM-TALL")
      (footprint "eagle-import:TACTILE_SWITCH_SMD_6.2MM_TALL")
      (libsource (lib "eagle-import") (part "MOMENTARY-SWITCH-SPST-SMD-6.2MM-TALL"))
    )
    (comp (ref "S3")
      (value "MOMENTARY-SWITCH-SPST-SMD-6.2MM-TALL")
      (footprint "eagle-import:TACTILE_SWITCH_SMD_6.2MM_TALL")
      (libsource (lib "eagle-import") (part "MOMENTARY-SWITCH-SPST-SMD-6.2MM-TALL"))
    )
    (comp (ref "S4")
      (value "MOMENTARY-SWITCH-SPST-SMD-6.2MM-TALL")
      (footprint "eagle-import:TACTILE_SWITCH_SMD_6.2MM_TALL")
      (libsource (lib "eagle-import") (part "MOMENTARY-SWITCH-SPST-SMD-6.2MM-TALL"))
    )
    (comp (ref "S5")
      (value "MOMENTARY-SWITCH-SPST-SMD-6.2MM-TALL")
      (footprint "eagle-import:TACTILE_SWITCH_SMD_6.2MM_TALL")
      (libsource (lib "eagle-import") (part "MOMENTARY-SWITCH-SPST-SMD-6.2MM-TALL"))
    )
    (comp (ref "S6")
      (value "MOMENTARY-SWITCH-SPST-SMD-6.2MM-TALL")
      (footprint "eagle-import:TACTILE_SWITCH_SMD_6.2MM_TALL")
      (libsource (lib "eagle-import") (part "MOMENTARY-SWITCH-SPST-SMD-6.2MM-TALL"))
    )
    (comp (ref "TP2")
      (value "TPB1,27")
      (footprint "eagle-import:B1,27")
      (libsource (lib "eagle-import") (part "TPB1,27"))
    )
    (comp (ref "TP3")
      (value "TPB1,27")
      (footprint "eagle-import:B1,27")
      (libsource (lib "eagle-import") (part "TPB1,27"))
    )
    (comp (ref "TP4")
      (value "TPB1,27")
      (footprint "eagle-import:B1,27")
      (libsource (lib "eagle-import") (part "TPB1,27"))
    )
    (comp (ref "TP5")
      (value "TPB1,27")
      (footprint "eagle-import:B1,27")
      (libsource (lib "eagle-import") (part "TPB1,27"))
    )
  )
  (nets
    (net (code "1") (name "+0V9") (class "Default")
      (node (ref "JP1") (pin "5") (pinfunction "5_5") (pintype "passive"))
      (node (ref "R15") (pin "1") (pinfunction "1_1") (pintype "passive"))
      (node (ref "R16") (pin "2") (pinfunction "2_2") (pintype "passive"))
      (node (ref "TP5") (pin "TP") (pinfunction "TP_TP") (pintype "input"))
    )
    (net (code "2") (name "+1V5") (class "Default")
      (node (ref "JP1") (pin "4") (pinfunction "4_4") (pintype "passive"))
      (node (ref "R13") (pin "1") (pinfunction "1_1") (pintype "passive"))
      (node (ref "R14") (pin "2") (pinfunction "2_2") (pintype "passive"))
      (node (ref "TP4") (pin "TP") (pinfunction "TP_TP") (pintype "input"))
    )
    (net (code "3") (name "+2V1") (class "Default")
      (node (ref "JP1") (pin "3") (pinfunction "3_3") (pintype "passive"))
      (node (ref "R11") (pin "1") (pinfunction "1_1") (pintype "passive"))
      (node (ref "R12") (pin "2") (pinfunction "2_2") (pintype "passive"))
      (node (ref "TP3") (pin "TP") (pinfunction "TP_TP") (pintype "input"))
    )
    (net (code "4") (name "+2V7") (class "Default")
      (node (ref "JP1") (pin "2") (pinfunction "2_2") (pintype "passive"))
      (node (ref "R10") (pin "2") (pinfunction "2_2") (pintype "passive"))
      (node (ref "R9") (pin "1") (pinfunction "1_1") (pintype "passive"))
      (node (ref "TP2") (pin "TP") (pinfunction "TP_TP") (pintype "input"))
    )
    (net (code "5") (name "+3V3") (class "Default")
      (node (ref "C10") (pin "1") (pinfunction "1_1") (pintype "passive"))
      (node (ref "C8") (pin "1") (pinfunction "1_1") (pintype "passive"))
      (node (ref "C9") (pin "1") (pinfunction "1_1") (pintype "passive"))
      (node (ref "JP1") (pin "1") (pinfunction "1_1") (pintype "passive"))
      (node (ref "JP3") (pin "1") (pinfunction "1_1") (pintype "passive"))
      (node (ref "JP3") (pin "3") (pinfunction "3_3") (pintype "passive"))
      (node (ref "JP3") (pin "5") (pinfunction "5_5") (pintype "passive"))
      (node (ref "JP3") (pin "7") (pinfunction "7_7") (pintype "passive"))
      (node (ref "R1") (pin "1") (pinfunction "1_1") (pintype "passive"))
      (node (ref "R11") (pin "2") (pinfunction "2_2") (pintype "passive"))
      (node (ref "R13") (pin "2") (pinfunction "2_2") (pintype "passive"))
      (node (ref "R15") (pin "2") (pinfunction "2_2") (pintype "passive"))
      (node (ref "R2") (pin "1") (pinfunction "1_1") (pintype "passive"))
      (node (ref "R21") (pin "2") (pinfunction "2_2") (pintype "passive"))
      (node (ref "R22") (pin "2") (pinfunction "2_2") (pintype "passive"))
      (node (ref "R23") (pin "2") (pinfunction "2_2") (pintype "passive"))
      (node (ref "R25") (pin "2") (pinfunction "2_2") (pintype "passive"))
      (node (ref "R27") (pin "2") (pinfunction "2_2") (pintype "passive"))
      (node (ref "R28") (pin "2") (pinfunction "2_2") (pintype "passive"))
      (node (ref "R29") (pin "2") (pinfunction "2_2") (pintype "passive"))
      (node (ref "R3") (pin "1") (pinfunction "1_1") (pintype "passive"))
      (node (ref "R30") (pin "2") (pinfunction "2_2") (pintype "passive"))
      (node (ref "R31") (pin "2") (pinfunction "2_2") (pintype "passive"))
      (node (ref "R4") (pin "1") (pinfunction "1_1") (pintype "passive"))
      (node (ref "R5") (pin "1") (pinfunction "1_1") (pintype "bidirectional"))
      (node (ref "R6") (pin "1") (pinfunction "1_1") (pintype "bidirectional"))
      (node (ref "R7") (pin "1") (pinfunction "1_1") (pintype "bidirectional"))
      (node (ref "R8") (pin "1") (pinfunction "1_1") (pintype "bidirectional"))
      (node (ref "R9") (pin "2") (pinfunction "2_2") (pintype "passive"))
      (node (ref "S10") (pin "B2") (pinfunction "2_B2") (pintype "passive"))
      (node (ref "S5") (pin "B2") (pinfunction "2_B2") (pintype "passive"))
      (node (ref "S6") (pin "B2") (pinfunction "2_B2") (pintype "passive"))
      (node (ref "S7") (pin "B2") (pinfunction "2_B2") (pintype "passive"))
      (node (ref "S8") (pin "B2") (pinfunction "2_B2") (pintype "passive"))
      (node (ref "S9") (pin "B2") (pinfunction "2_B2") (pintype "passive"))
      (node (ref "U1") (pin "1") (pinfunction "3V3_1") (pintype "power_in"))
      (node (ref "U4") (pin "8") (pinfunction "VDD_8") (pintype "power_in"))
      (node (ref "U5") (pin "5") (pinfunction "VCC_5") (pintype "power_in"))
      (node (ref "U6") (pin "5") (pinfunction "VCC_5") (pintype "power_in"))
      (node (ref "U6") (pin "6") (pinfunction "A0_6") (pintype "input"))
      (node (ref "X6") (pin "3") (pinfunction "KL_3") (pintype "passive"))
    )
    (net (code "6") (name "+5V") (class "Default")
      (node (ref "C5") (pin "1") (pinfunction "1_1") (pintype "passive"))
      (node (ref "C6") (pin "1") (pinfunction "1_1") (pintype "passive"))
      (node (ref "C7") (pin "1") (pinfunction "1_1") (pintype "passive"))
      (node (ref "L1") (pin "2") (pinfunction "2_2") (pintype "bidirectional"))
      (node (ref "R17") (pin "2") (pinfunction "2_2") (pintype "passive"))
      (node (ref "R24") (pin "2") (pinfunction "2_2") (pintype "passive"))
      (node (ref "TP6") (pin "TP") (pinfunction "TP_TP") (pintype "input"))
      (node (ref "U1") (pin "19") (pinfunction "EXT_5V_19") (pintype "power_in"))
      (node (ref "U3") (pin "19") (pinfunction "V+_19") (pintype "bidirectional"))
      (node (ref "X2") (pin "1") (pinfunction "KL_1") (pintype "passive"))
      (node (ref "X3") (pin "1") (pinfunction "KL_1") (pintype "passive"))
    )
    (net (code "7") (name "+12V") (class "Default")
      (node (ref "D1") (pin "C") (pinfunction "C_C") (pintype "passive"))
      (node (ref "F1") (pin "1") (pinfunction "1_1") (pintype "passive"))
      (node (ref "X1") (pin "1") (pinfunction "KL_1") (pintype "passive"))
      (node (ref "X5") (pin "1") (pinfunction "KL_1") (pintype "passive"))
    )
    (net (code "8") (name "ADC_RDY") (class "Default")
      (node (ref "R25") (pin "1") (pinfunction "1_1") (pintype "passive"))
      (node (ref "TP14") (pin "TP") (pinfunction "TP_TP") (pintype "input"))
      (node (ref "U1") (pin "32") (pinfunction "IO4_32") (pintype "bidirectional"))
      (node (ref "U4") (pin "2") (pinfunction "ALERT/RDY_2") (pintype "open_collector"))
    )
    (net (code "9") (name "BUTTON_0") (class "Default")
      (node (ref "R19") (pin "2") (pinfunction "2_2") (pintype "passive"))
      (node (ref "S5") (pin "A2") (pinfunction "1_A2") (pintype "passive"))
      (node (ref "U1") (pin "31") (pinfunction "IO16_31") (pintype "bidirectional"))
    )
    (net (code "10") (name "BUTTON_1") (class "Default")
      (node (ref "R20") (pin "2") (pinfunction "2_2") (pintype "passive"))
      (node (ref "S6") (pin "A2") (pinfunction "1_A2") (pintype "passive"))
      (node (ref "U1") (pin "30") (pinfunction "IO17_30") (pintype "bidirectional"))
    )
    (net (code "11") (name "CS_MAX7219_LEDM") (class "Default")
      (node (ref "TP17") (pin "TP") (pinfunction "TP_TP") (pintype "input"))
      (node (ref "U1") (pin "13") (pinfunction "IO12_13") (pintype "bidirectional"))
      (node (ref "X4") (pin "1") (pinfunction "KL_1") (pintype "passive"))
    )
    (net (code "12") (name "CS_MAX7221_7SEG") (class "Default")
      (node (ref "TP13") (pin "TP") (pinfunction "TP_TP") (pintype "input"))
      (node (ref "U1") (pin "29") (pinfunction "IO5_29") (pintype "bidirectional"))
      (node (ref "U3") (pin "12") (pinfunction "~{CS}_12") (pintype "bidirectional"))
    )
    (net (code "13") (name "DIG_0") (class "Default")
      (node (ref "DS1") (pin "1") (pinfunction "COMMON_CATHODE_D1_1") (pintype "bidirectional"))
      (node (ref "U3") (pin "2") (pinfunction "DIG_0_2") (pintype "bidirectional"))
    )
    (net (code "14") (name "DIG_1") (class "Default")
      (node (ref "DS1") (pin "2") (pinfunction "COMMON_CATHODE_D2_2") (pintype "bidirectional"))
      (node (ref "U3") (pin "11") (pinfunction "DIG_1_11") (pintype "bidirectional"))
    )
    (net (code "15") (name "DIG_2") (class "Default")
      (node (ref "DS1") (pin "6") (pinfunction "COMMON_CATHODE_D3_6") (pintype "bidirectional"))
      (node (ref "U3") (pin "6") (pinfunction "DIG_2_6") (pintype "bidirectional"))
    )
    (net (code "16") (name "DIG_3") (class "Default")
      (node (ref "DS1") (pin "8") (pinfunction "COMMON_CATHODE_D4_8") (pintype "bidirectional"))
      (node (ref "U3") (pin "7") (pinfunction "DIG_3_7") (pintype "bidirectional"))
    )
    (net (code "17") (name "GND") (class "Default")
      (node (ref "C1") (pin "2") (pinfunction "2_2") (pintype "passive"))
      (node (ref "C10") (pin "2") (pinfunction "2_2") (pintype "passive"))
      (node (ref "C2") (pin "2") (pinfunction "2_2") (pintype "passive"))
      (node (ref "C3") (pin "2") (pinfunction "2_2") (pintype "passive"))
      (node (ref "C5") (pin "2") (pinfunction "2_2") (pintype "passive"))
      (node (ref "C6") (pin "2") (pinfunction "2_2") (pintype "passive"))
      (node (ref "C7") (pin "2") (pinfunction "2_2") (pintype "passive"))
      (node (ref "C8") (pin "2") (pinfunction "2_2") (pintype "passive"))
      (node (ref "C9") (pin "2") (pinfunction "2_2") (pintype "passive"))
      (node (ref "JP3") (pin "2") (pinfunction "2_2") (pintype "passive"))
      (node (ref "JP3") (pin "4") (pinfunction "4_4") (pintype "passive"))
      (node (ref "JP3") (pin "6") (pinfunction "6_6") (pintype "passive"))
      (node (ref "JP3") (pin "8") (pinfunction "8_8") (pintype "passive"))
      (node (ref "LS1") (pin "2") (pinfunction "2_2") (pintype "bidirectional"))
      (node (ref "Q2") (pin "3") (pinfunction "S_3") (pintype "bidirectional"))
      (node (ref "R10") (pin "1") (pinfunction "1_1") (pintype "passive"))
      (node (ref "R12") (pin "1") (pinfunction "1_1") (pintype "passive"))
      (node (ref "R14") (pin "1") (pinfunction "1_1") (pintype "passive"))
      (node (ref "R16") (pin "1") (pinfunction "1_1") (pintype "passive"))
      (node (ref "R18") (pin "1") (pinfunction "1_1") (pintype "passive"))
      (node (ref "R19") (pin "1") (pinfunction "1_1") (pintype "passive"))
      (node (ref "R20") (pin "1") (pinfunction "1_1") (pintype "passive"))
      (node (ref "R26") (pin "1") (pinfunction "1_1") (pintype "passive"))
      (node (ref "R26") (pin "2") (pinfunction "2_2") (pintype "passive"))
      (node (ref "R32") (pin "1") (pinfunction "1_1") (pintype "passive"))
      (node (ref "R33") (pin "1") (pinfunction "1_1") (pintype "passive"))
      (node (ref "R34") (pin "1") (pinfunction "1_1") (pintype "passive"))
      (node (ref "R35") (pin "1") (pinfunction "1_1") (pintype "passive"))
      (node (ref "R36") (pin "1") (pinfunction "1_1") (pintype "passive"))
      (node (ref "R5") (pin "3") (pinfunction "3_3") (pintype "bidirectional"))
      (node (ref "R5") (pin "4") (pinfunction "MNT_1_4") (pintype "bidirectional"))
      (node (ref "R5") (pin "5") (pinfunction "MNT_2_5") (pintype "bidirectional"))
      (node (ref "R6") (pin "3") (pinfunction "3_3") (pintype "bidirectional"))
      (node (ref "R6") (pin "4") (pinfunction "MNT_1_4") (pintype "bidirectional"))
      (node (ref "R6") (pin "5") (pinfunction "MNT_2_5") (pintype "bidirectional"))
      (node (ref "R7") (pin "3") (pinfunction "3_3") (pintype "bidirectional"))
      (node (ref "R7") (pin "4") (pinfunction "MNT_1_4") (pintype "bidirectional"))
      (node (ref "R7") (pin "5") (pinfunction "MNT_2_5") (pintype "bidirectional"))
      (node (ref "R8") (pin "3") (pinfunction "3_3") (pintype "bidirectional"))
      (node (ref "R8") (pin "4") (pinfunction "MNT_1_4") (pintype "bidirectional"))
      (node (ref "R8") (pin "5") (pinfunction "MNT_2_5") (pintype "bidirectional"))
      (node (ref "S1") (pin "B2") (pinfunction "2_B2") (pintype "passive"))
      (node (ref "S2") (pin "B2") (pinfunction "2_B2") (pintype "passive"))
      (node (ref "S3") (pin "B2") (pinfunction "2_B2") (pintype "passive"))
      (node (ref "S4") (pin "B2") (pinfunction "2_B2") (pintype "passive"))
      (node (ref "TP7") (pin "TP") (pinfunction "TP_TP") (pintype "input"))
      (node (ref "U1") (pin "14") (pinfunction "GND1_14") (pintype "power_in"))
      (node (ref "U1") (pin "20") (pinfunction "GND3_20") (pintype "power_in"))
      (node (ref "U1") (pin "26") (pinfunction "GND2_26") (pintype "power_in"))
      (node (ref "U2") (pin "1") (pinfunction "GND_1") (pintype "power_in"))
      (node (ref "U3") (pin "4") (pinfunction "1_GND_4") (pintype "bidirectional"))
      (node (ref "U3") (pin "9") (pinfunction "2_GND_9") (pintype "bidirectional"))
      (node (ref "U4") (pin "1") (pinfunction "ADDR_1") (pintype "input"))
      (node (ref "U4") (pin "3") (pinfunction "GND_3") (pintype "power_in"))
      (node (ref "U5") (pin "15") (pinfunction "GND_15") (pintype "power_in"))
      (node (ref "U5") (pin "6") (pinfunction "A0_6") (pintype "input"))
      (node (ref "U5") (pin "7") (pinfunction "A1_7") (pintype "input"))
      (node (ref "U5") (pin "9") (pinfunction "A2_9") (pintype "input"))
      (node (ref "U6") (pin "15") (pinfunction "GND_15") (pintype "power_in"))
      (node (ref "U6") (pin "7") (pinfunction "A1_7") (pintype "input"))
      (node (ref "U6") (pin "9") (pinfunction "A2_9") (pintype "input"))
      (node (ref "X1") (pin "2") (pinfunction "KL_2") (pintype "passive"))
      (node (ref "X2") (pin "3") (pinfunction "KL_3") (pintype "passive"))
      (node (ref "X3") (pin "2") (pinfunction "KL_2") (pintype "passive"))
      (node (ref "X6") (pin "1") (pinfunction "KL_1") (pintype "passive"))
    )
    (net (code "18") (name "LASER_SENSE") (class "Default")
      (node (ref "U1") (pin "10") (pinfunction "IO26_10") (pintype "bidirectional"))
      (node (ref "X6") (pin "2") (pinfunction "KL_2") (pintype "passive"))
    )
    (net (code "19") (name "LED_RING") (class "Default")
      (node (ref "U1") (pin "11") (pinfunction "IO27_11") (pintype "bidirectional"))
      (node (ref "X2") (pin "2") (pinfunction "KL_2") (pintype "passive"))
    )
    (net (code "20") (name "LOCK_0") (class "Default")
      (node (ref "Q2") (pin "1") (pinfunction "G_1") (pintype "bidirectional"))
      (node (ref "R36") (pin "2") (pinfunction "2_2") (pintype "passive"))
      (node (ref "U1") (pin "12") (pinfunction "IO14_12") (pintype "bidirectional"))
    )
    (net (code "21") (name "Net-(LED1-PadA)") (class "Default")
      (node (ref "LED1") (pin "A") (pinfunction "A_A") (pintype "passive"))
      (node (ref "R1") (pin "2") (pinfunction "2_2") (pintype "passive"))
    )
    (net (code "22") (name "Net-(LED2-PadA)") (class "Default")
      (node (ref "LED2") (pin "A") (pinfunction "A_A") (pintype "passive"))
      (node (ref "R2") (pin "2") (pinfunction "2_2") (pintype "passive"))
    )
    (net (code "23") (name "Net-(LED3-PadA)") (class "Default")
      (node (ref "LED3") (pin "A") (pinfunction "A_A") (pintype "passive"))
      (node (ref "R3") (pin "2") (pinfunction "2_2") (pintype "passive"))
    )
    (net (code "24") (name "Net-(LED4-PadA)") (class "Default")
      (node (ref "LED4") (pin "A") (pinfunction "A_A") (pintype "passive"))
      (node (ref "R4") (pin "2") (pinfunction "2_2") (pintype "passive"))
    )
    (net (code "25") (name "Net-(LED5-PadA)") (class "Default")
      (node (ref "LED5") (pin "A") (pinfunction "A_A") (pintype "passive"))
      (node (ref "R28") (pin "1") (pinfunction "1_1") (pintype "passive"))
    )
    (net (code "26") (name "Net-(LED6-PadA)") (class "Default")
      (node (ref "LED6") (pin "A") (pinfunction "A_A") (pintype "passive"))
      (node (ref "R29") (pin "1") (pinfunction "1_1") (pintype "passive"))
    )
    (net (code "27") (name "Net-(LED7-PadA)") (class "Default")
      (node (ref "LED7") (pin "A") (pinfunction "A_A") (pintype "passive"))
      (node (ref "R30") (pin "1") (pinfunction "1_1") (pintype "passive"))
    )
    (net (code "28") (name "Net-(LED8-PadA)") (class "Default")
      (node (ref "LED8") (pin "A") (pinfunction "A_A") (pintype "passive"))
      (node (ref "R31") (pin "1") (pinfunction "1_1") (pintype "passive"))
    )
    (net (code "29") (name "Net-(Q2-D)") (class "Default")
      (node (ref "D1") (pin "A") (pinfunction "A_A") (pintype "passive"))
      (node (ref "Q2") (pin "2") (pinfunction "D_2") (pintype "bidirectional"))
      (node (ref "X5") (pin "2") (pinfunction "KL_2") (pintype "passive"))
    )
    (net (code "30") (name "Net-(S1-1)") (class "Default")
      (node (ref "LED1") (pin "C") (pinfunction "C_C") (pintype "passive"))
      (node (ref "S1") (pin "A2") (pinfunction "1_A2") (pintype "passive"))
    )
    (net (code "31") (name "Net-(S2-1)") (class "Default")
      (node (ref "LED2") (pin "C") (pinfunction "C_C") (pintype "passive"))
      (node (ref "S2") (pin "A2") (pinfunction "1_A2") (pintype "passive"))
    )
    (net (code "32") (name "Net-(S3-1)") (class "Default")
      (node (ref "LED3") (pin "C") (pinfunction "C_C") (pintype "passive"))
      (node (ref "S3") (pin "A2") (pinfunction "1_A2") (pintype "passive"))
    )
    (net (code "33") (name "Net-(S4-1)") (class "Default")
      (node (ref "LED4") (pin "C") (pinfunction "C_C") (pintype "passive"))
      (node (ref "S4") (pin "A2") (pinfunction "1_A2") (pintype "passive"))
    )
    (net (code "34") (name "Net-(U2-EN)") (class "Default")
      (node (ref "C1") (pin "1") (pinfunction "1_1") (pintype "passive"))
      (node (ref "C2") (pin "1") (pinfunction "1_1") (pintype "passive"))
      (node (ref "C3") (pin "1") (pinfunction "1_1") (pintype "passive"))
      (node (ref "F1") (pin "2") (pinfunction "2_2") (pintype "passive"))
      (node (ref "TP1") (pin "TP") (pinfunction "TP_TP") (pintype "input"))
      (node (ref "U2") (pin "3") (pinfunction "VIN_3") (pintype "power_in"))
      (node (ref "U2") (pin "5") (pinfunction "EN_5") (pintype "input"))
    )
    (net (code "35") (name "Net-(U2-SW)") (class "Default")
      (node (ref "C4") (pin "2") (pinfunction "2_2") (pintype "passive"))
      (node (ref "L1") (pin "1") (pinfunction "1_1") (pintype "bidirectional"))
      (node (ref "U2") (pin "2") (pinfunction "SW_2") (pintype "output"))
    )
    (net (code "36") (name "Net-(U2-VBST)") (class "Default")
      (node (ref "C4") (pin "1") (pinfunction "1_1") (pintype "passive"))
      (node (ref "U2") (pin "6") (pinfunction "VBST_6") (pintype "output"))
    )
    (net (code "37") (name "Net-(U2-VFB)") (class "Default")
      (node (ref "R17") (pin "1") (pinfunction "1_1") (pintype "passive"))
      (node (ref "R18") (pin "2") (pinfunction "2_2") (pintype "passive"))
      (node (ref "TP8") (pin "TP") (pinfunction "TP_TP") (pintype "input"))
      (node (ref "U2") (pin "4") (pinfunction "VFB_4") (pintype "input"))
    )
    (net (code "38") (name "Net-(U3-ISET)") (class "Default")
      (node (ref "R24") (pin "1") (pinfunction "1_1") (pintype "passive"))
      (node (ref "U3") (pin "18") (pinfunction "ISET_18") (pintype "bidirectional"))
    )
    (net (code "39") (name "Net-(U5-P0)") (class "Default")
      (node (ref "JP4") (pin "1") (pinfunction "1_1") (pintype "passive"))
      (node (ref "U5") (pin "10") (pinfunction "P0_10") (pintype "bidirectional"))
    )
    (net (code "40") (name "Net-(U5-P1)") (class "Default")
      (node (ref "JP4") (pin "2") (pinfunction "2_2") (pintype "passive"))
      (node (ref "U5") (pin "11") (pinfunction "P1_11") (pintype "bidirectional"))
    )
    (net (code "41") (name "Net-(U5-P2)") (class "Default")
      (node (ref "JP4") (pin "3") (pinfunction "3_3") (pintype "passive"))
      (node (ref "U5") (pin "12") (pinfunction "P2_12") (pintype "bidirectional"))
    )
    (net (code "42") (name "Net-(U5-P3)") (class "Default")
      (node (ref "JP4") (pin "4") (pinfunction "4_4") (pintype "passive"))
      (node (ref "U5") (pin "14") (pinfunction "P3_14") (pintype "bidirectional"))
    )
    (net (code "43") (name "Net-(U5-P4)") (class "Default")
      (node (ref "JP4") (pin "5") (pinfunction "5_5") (pintype "passive"))
      (node (ref "U5") (pin "16") (pinfunction "P4_16") (pintype "bidirectional"))
    )
    (net (code "44") (name "Net-(U5-P5)") (class "Default")
      (node (ref "JP4") (pin "6") (pinfunction "6_6") (pintype "passive"))
      (node (ref "U5") (pin "17") (pinfunction "P5_17") (pintype "bidirectional"))
    )
    (net (code "45") (name "Net-(U5-P6)") (class "Default")
      (node (ref "JP4") (pin "7") (pinfunction "7_7") (pintype "passive"))
      (node (ref "U5") (pin "19") (pinfunction "P6_19") (pintype "bidirectional"))
    )
    (net (code "46") (name "Net-(U5-P7)") (class "Default")
      (node (ref "JP4") (pin "8") (pinfunction "8_8") (pintype "passive"))
      (node (ref "U5") (pin "20") (pinfunction "P7_20") (pintype "bidirectional"))
    )
    (net (code "47") (name "Net-(U6-P0)") (class "Default")
      (node (ref "LED5") (pin "C") (pinfunction "C_C") (pintype "passive"))
      (node (ref "U6") (pin "10") (pinfunction "P0_10") (pintype "bidirectional"))
    )
    (net (code "48") (name "Net-(U6-P1)") (class "Default")
      (node (ref "LED6") (pin "C") (pinfunction "C_C") (pintype "passive"))
      (node (ref "U6") (pin "11") (pinfunction "P1_11") (pintype "bidirectional"))
    )
    (net (code "49") (name "Net-(U6-P2)") (class "Default")
      (node (ref "LED7") (pin "C") (pinfunction "C_C") (pintype "passive"))
      (node (ref "U6") (pin "12") (pinfunction "P2_12") (pintype "bidirectional"))
    )
    (net (code "50") (name "Net-(U6-P3)") (class "Default")
      (node (ref "LED8") (pin "C") (pinfunction "C_C") (pintype "passive"))
      (node (ref "U6") (pin "14") (pinfunction "P3_14") (pintype "bidirectional"))
    )
    (net (code "51") (name "P4_BTN7") (class "Default")
      (node (ref "R32") (pin "2") (pinfunction "2_2") (pintype "passive"))
      (node (ref "S7") (pin "A2") (pinfunction "1_A2") (pintype "passive"))
      (node (ref "U6") (pin "16") (pinfunction "P4_16") (pintype "bidirectional"))
    )
    (net (code "52") (name "P5_BTN8") (class "Default")
      (node (ref "R33") (pin "2") (pinfunction "2_2") (pintype "passive"))
      (node (ref "S8") (pin "A2") (pinfunction "1_A2") (pintype "passive"))
      (node (ref "U6") (pin "17") (pinfunction "P5_17") (pintype "bidirectional"))
    )
    (net (code "53") (name "P6_BTN9") (class "Default")
      (node (ref "R34") (pin "2") (pinfunction "2_2") (pintype "passive"))
      (node (ref "S9") (pin "A2") (pinfunction "1_A2") (pintype "passive"))
      (node (ref "U6") (pin "19") (pinfunction "P6_19") (pintype "bidirectional"))
    )
    (net (code "54") (name "P7_BTN10") (class "Default")
      (node (ref "R35") (pin "2") (pinfunction "2_2") (pintype "passive"))
      (node (ref "S10") (pin "A2") (pinfunction "1_A2") (pintype "passive"))
      (node (ref "U6") (pin "20") (pinfunction "P7_20") (pintype "bidirectional"))
    )
    (net (code "55") (name "PCF_INT_0") (class "Default")
      (node (ref "R23") (pin "1") (pinfunction "1_1") (pintype "passive"))
      (node (ref "TP16") (pin "TP") (pinfunction "TP_TP") (pintype "input"))
      (node (ref "U1") (pin "4") (pinfunction "SENSOR_VN_4") (pintype "input"))
      (node (ref "U5") (pin "1") (pinfunction "~{INT}_1") (pintype "open_collector"))
    )
    (net (code "56") (name "PCF_INT_1") (class "Default")
      (node (ref "R27") (pin "1") (pinfunction "1_1") (pintype "passive"))
      (node (ref "TP15") (pin "TP") (pinfunction "TP_TP") (pintype "input"))
      (node (ref "U1") (pin "3") (pinfunction "SENSOR_VP_3") (pintype "input"))
      (node (ref "U6") (pin "1") (pinfunction "~{INT}_1") (pintype "open_collector"))
    )
    (net (code "57") (name "PIEZO_0") (class "Default")
      (node (ref "LS1") (pin "1") (pinfunction "1_1") (pintype "bidirectional"))
      (node (ref "U1") (pin "15") (pinfunction "IO13_15") (pintype "bidirectional"))
    )
    (net (code "58") (name "POTI_0") (class "Default")
      (node (ref "R5") (pin "2") (pinfunction "2_2") (pintype "bidirectional"))
      (node (ref "U4") (pin "4") (pinfunction "AIN0_4") (pintype "input"))
    )
    (net (code "59") (name "POTI_1") (class "Default")
      (node (ref "R6") (pin "2") (pinfunction "2_2") (pintype "bidirectional"))
      (node (ref "U4") (pin "5") (pinfunction "AIN1_5") (pintype "input"))
    )
    (net (code "60") (name "POTI_2") (class "Default")
      (node (ref "R7") (pin "2") (pinfunction "2_2") (pintype "bidirectional"))
      (node (ref "U4") (pin "6") (pinfunction "AIN2_6") (pintype "input"))
    )
    (net (code "61") (name "POTI_3") (class "Default")
      (node (ref "R8") (pin "2") (pinfunction "2_2") (pintype "bidirectional"))
      (node (ref "U4") (pin "7") (pinfunction "AIN3_7") (pintype "input"))
    )
    (net (code "62") (name "REWIRE_0_0") (class "Default")
      (node (ref "JP2") (pin "1") (pinfunction "1_1") (pintype "passive"))
      (node (ref "U1") (pin "9") (pinfunction "IO25_9") (pintype "bidirectional"))
    )
    (net (code "63") (name "REWIRE_0_1") (class "Default")
      (node (ref "JP2") (pin "2") (pinfunction "2_2") (pintype "passive"))
      (node (ref "U1") (pin "8") (pinfunction "IO33_8") (pintype "bidirectional"))
    )
    (net (code "64") (name "REWIRE_0_2") (class "Default")
      (node (ref "JP2") (pin "3") (pinfunction "3_3") (pintype "passive"))
      (node (ref "U1") (pin "7") (pinfunction "IO32_7") (pintype "bidirectional"))
    )
    (net (code "65") (name "REWIRE_0_3") (class "Default")
      (node (ref "JP2") (pin "4") (pinfunction "4_4") (pintype "passive"))
      (node (ref "U1") (pin "6") (pinfunction "IO35_6") (pintype "bidirectional"))
    )
    (net (code "66") (name "REWIRE_0_4") (class "Default")
      (node (ref "JP2") (pin "5") (pinfunction "5_5") (pintype "passive"))
      (node (ref "U1") (pin "5") (pinfunction "IO34_5") (pintype "bidirectional"))
    )
    (net (code "67") (name "SCL") (class "Default")
      (node (ref "R21") (pin "1") (pinfunction "1_1") (pintype "passive"))
      (node (ref "TP10") (pin "TP") (pinfunction "TP_TP") (pintype "input"))
      (node (ref "U1") (pin "22") (pinfunction "IO22_22") (pintype "bidirectional"))
      (node (ref "U4") (pin "10") (pinfunction "SCL_10") (pintype "input"))
      (node (ref "U5") (pin "2") (pinfunction "SCL_2") (pintype "input"))
      (node (ref "U6") (pin "2") (pinfunction "SCL_2") (pintype "input"))
    )
    (net (code "68") (name "SDA") (class "Default")
      (node (ref "R22") (pin "1") (pinfunction "1_1") (pintype "passive"))
      (node (ref "TP11") (pin "TP") (pinfunction "TP_TP") (pintype "input"))
      (node (ref "U1") (pin "25") (pinfunction "IO21_25") (pintype "bidirectional"))
      (node (ref "U4") (pin "9") (pinfunction "SDA_9") (pintype "bidirectional"))
      (node (ref "U5") (pin "4") (pinfunction "SDA_4") (pintype "bidirectional"))
      (node (ref "U6") (pin "4") (pinfunction "SDA_4") (pintype "bidirectional"))
    )
    (net (code "69") (name "SEG_A") (class "Default")
      (node (ref "DS1") (pin "14") (pinfunction "ANODE_A_14") (pintype "bidirectional"))
      (node (ref "U3") (pin "14") (pinfunction "SEG_A_14") (pintype "bidirectional"))
    )
    (net (code "70") (name "SEG_B") (class "Default")
      (node (ref "DS1") (pin "16") (pinfunction "ANODE_B_16") (pintype "bidirectional"))
      (node (ref "U3") (pin "16") (pinfunction "SEG_B_16") (pintype "bidirectional"))
    )
    (net (code "71") (name "SEG_C") (class "Default")
      (node (ref "DS1") (pin "13") (pinfunction "ANODE_C_13") (pintype "bidirectional"))
      (node (ref "U3") (pin "20") (pinfunction "SEG_C_20") (pintype "bidirectional"))
    )
    (net (code "72") (name "SEG_D") (class "Default")
      (node (ref "DS1") (pin "3") (pinfunction "ANODE_D_3") (pintype "bidirectional"))
      (node (ref "U3") (pin "23") (pinfunction "SEG_D_23") (pintype "bidirectional"))
    )
    (net (code "73") (name "SEG_DP") (class "Default")
      (node (ref "DS1") (pin "7") (pinfunction "ANODE_DP_7") (pintype "bidirectional"))
      (node (ref "U3") (pin "22") (pinfunction "SEG_DP_22") (pintype "bidirectional"))
    )
    (net (code "74") (name "SEG_E") (class "Default")
      (node (ref "DS1") (pin "5") (pinfunction "ANODE_E_5") (pintype "bidirectional"))
      (node (ref "U3") (pin "21") (pinfunction "SEG_E_21") (pintype "bidirectional"))
    )
    (net (code "75") (name "SEG_F") (class "Default")
      (node (ref "DS1") (pin "11") (pinfunction "ANODE_F_11") (pintype "bidirectional"))
      (node (ref "U3") (pin "15") (pinfunction "SEG_F_15") (pintype "bidirectional"))
    )
    (net (code "76") (name "SEG_G") (class "Default")
      (node (ref "DS1") (pin "15") (pinfunction "ANODE_G_15") (pintype "bidirectional"))
      (node (ref "U3") (pin "17") (pinfunction "SEG_G_17") (pintype "bidirectional"))
    )
    (net (code "77") (name "SPI_CLK") (class "Default")
      (node (ref "TP9") (pin "TP") (pinfunction "TP_TP") (pintype "input"))
      (node (ref "U1") (pin "28") (pinfunction "IO18_28") (pintype "bidirectional"))
      (node (ref "U3") (pin "13") (pinfunction "CLK_13") (pintype "bidirectional"))
      (node (ref "X4") (pin "2") (pinfunction "KL_2") (pintype "passive"))
    )
    (net (code "78") (name "SPI_MOSI") (class "Default")
      (node (ref "TP12") (pin "TP") (pinfunction "TP_TP") (pintype "input"))
      (node (ref "U1") (pin "21") (pinfunction "IO23_21") (pintype "bidirectional"))
      (node (ref "U3") (pin "1") (pinfunction "DIN_1") (pintype "bidirectional"))
      (node (ref "X4") (pin "3") (pinfunction "KL_3") (pintype "passive"))
    )
    (net (code "79") (name "unconnected-(DS1-ANODE_L1{slash}L2-Pad12)") (class "Default")
      (node (ref "DS1") (pin "12") (pinfunction "ANODE_L1/L2_12") (pintype "bidirectional"))
    )
    (net (code "80") (name "unconnected-(DS1-ANODE_L3-Pad9)") (class "Default")
      (node (ref "DS1") (pin "9") (pinfunction "ANODE_L3_9") (pintype "bidirectional"))
    )
    (net (code "81") (name "unconnected-(DS1-CATHODE_L3-Pad10)") (class "Default")
      (node (ref "DS1") (pin "10") (pinfunction "CATHODE_L3_10") (pintype "bidirectional"))
    )
    (net (code "82") (name "unconnected-(DS1-COMMON_CATHODE_L1{slash}L2-Pad4)") (class "Default")
      (node (ref "DS1") (pin "4") (pinfunction "COMMON_CATHODE_L1/L2_4") (pintype "bidirectional"))
    )
    (net (code "83") (name "unconnected-(U1-CLK-Pad38)") (class "Default")
      (node (ref "U1") (pin "38") (pinfunction "CLK_38") (pintype "input"))
    )
    (net (code "84") (name "unconnected-(U1-CMD-Pad18)") (class "Default")
      (node (ref "U1") (pin "18") (pinfunction "CMD_18") (pintype "bidirectional"))
    )
    (net (code "85") (name "unconnected-(U1-EN-Pad2)") (class "Default")
      (node (ref "U1") (pin "2") (pinfunction "EN_2") (pintype "input"))
    )
    (net (code "86") (name "unconnected-(U1-IO0-Pad33)") (class "Default")
      (node (ref "U1") (pin "33") (pinfunction "IO0_33") (pintype "bidirectional"))
    )
    (net (code "87") (name "unconnected-(U1-IO2-Pad34)") (class "Default")
      (node (ref "U1") (pin "34") (pinfunction "IO2_34") (pintype "bidirectional"))
    )
    (net (code "88") (name "unconnected-(U1-IO15-Pad35)") (class "Default")
      (node (ref "U1") (pin "35") (pinfunction "IO15_35") (pintype "bidirectional"))
    )
    (net (code "89") (name "unconnected-(U1-IO19-Pad27)") (class "Default")
      (node (ref "U1") (pin "27") (pinfunction "IO19_27") (pintype "bidirectional"))
    )
    (net (code "90") (name "unconnected-(U1-RXD0-Pad24)") (class "Default")
      (node (ref "U1") (pin "24") (pinfunction "RXD0_24") (pintype "input"))
    )
    (net (code "91") (name "unconnected-(U1-SD0-Pad37)") (class "Default")
      (node (ref "U1") (pin "37") (pinfunction "SD0_37") (pintype "bidirectional"))
    )
    (net (code "92") (name "unconnected-(U1-SD1-Pad36)") (class "Default")
      (node (ref "U1") (pin "36") (pinfunction "SD1_36") (pintype "bidirectional"))
    )
    (net (code "93") (name "unconnected-(U1-SD2-Pad16)") (class "Default")
      (node (ref "U1") (pin "16") (pinfunction "SD2_16") (pintype "bidirectional"))
    )
    (net (code "94") (name "unconnected-(U1-SD3-Pad17)") (class "Default")
      (node (ref "U1") (pin "17") (pinfunction "SD3_17") (pintype "bidirectional"))
    )
    (net (code "95") (name "unconnected-(U1-TXD0-Pad23)") (class "Default")
      (node (ref "U1") (pin "23") (pinfunction "TXD0_23") (pintype "output"))
    )
    (net (code "96") (name "unconnected-(U3-DIG_4-Pad3)") (class "Default")
      (node (ref "U3") (pin "3") (pinfunction "DIG_4_3") (pintype "bidirectional"))
    )
    (net (code "97") (name "unconnected-(U3-DIG_5-Pad10)") (class "Default")
      (node (ref "U3") (pin "10") (pinfunction "DIG_5_10") (pintype "bidirectional"))
    )
    (net (code "98") (name "unconnected-(U3-DIG_6-Pad5)") (class "Default")
      (node (ref "U3") (pin "5") (pinfunction "DIG_6_5") (pintype "bidirectional"))
    )
    (net (code "99") (name "unconnected-(U3-DIG_7-Pad8)") (class "Default")
      (node (ref "U3") (pin "8") (pinfunction "DIG_7_8") (pintype "bidirectional"))
    )
    (net (code "100") (name "unconnected-(U3-DOUT-Pad24)") (class "Default")
      (node (ref "U3") (pin "24") (pinfunction "DOUT_24") (pintype "bidirectional"))
    )
    (net (code "101") (name "unconnected-(U5-1_NC-Pad13)") (class "Default")
      (node (ref "U5") (pin "13") (pinfunction "1_NC_13") (pintype "passive"))
    )
    (net (code "102") (name "unconnected-(U5-2_NC-Pad18)") (class "Default")
      (node (ref "U5") (pin "18") (pinfunction "2_NC_18") (pintype "passive"))
    )
    (net (code "103") (name "unconnected-(U5-3_NC-Pad3)") (class "Default")
      (node (ref "U5") (pin "3") (pinfunction "3_NC_3") (pintype "passive"))
    )
    (net (code "104") (name "unconnected-(U5-4_NC-Pad8)") (class "Default")
      (node (ref "U5") (pin "8") (pinfunction "4_NC_8") (pintype "passive"))
    )
    (net (code "105") (name "unconnected-(U6-1_NC-Pad13)") (class "Default")
      (node (ref "U6") (pin "13") (pinfunction "1_NC_13") (pintype "passive"))
    )
    (net (code "106") (name "unconnected-(U6-2_NC-Pad18)") (class "Default")
      (node (ref "U6") (pin "18") (pinfunction "2_NC_18") (pintype "passive"))
    )
    (net (code "107") (name "unconnected-(U6-3_NC-Pad3)") (class "Default")
      (node (ref "U6") (pin "3") (pinfunction "3_NC_3") (pintype "passive"))
    )
    (net (code "108") (name "unconnected-(U6-4_NC-Pad8)") (class "Default")
      (node (ref "U6") (pin "8") (pinfunction "4_NC_8") (pintype "passive"))
    )
  )
)
